# Test.net
KiCad netlist of a schematic drawn in Altium Designer
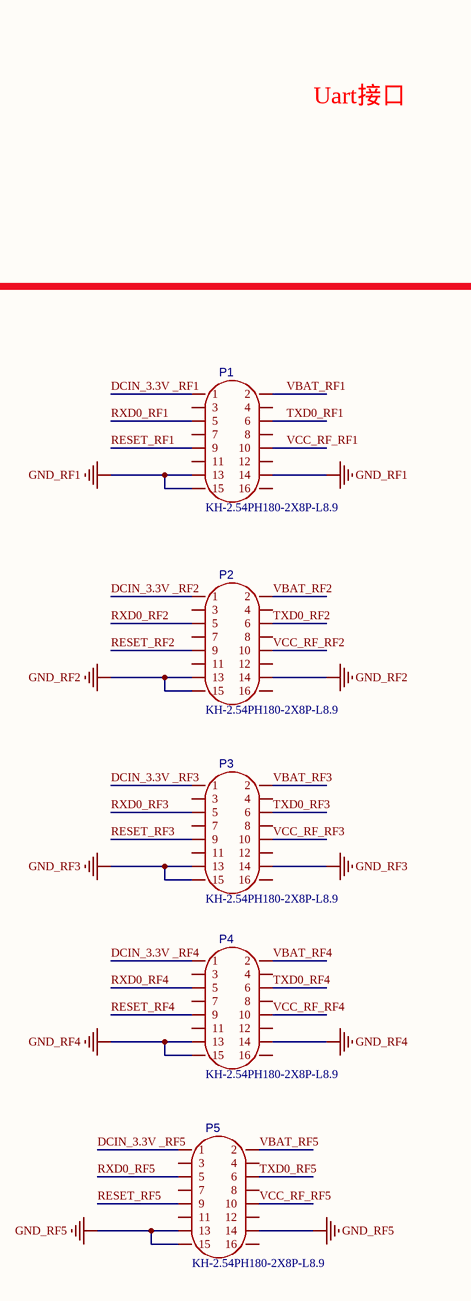
[diagram p0: Test.SchDoc, top left]
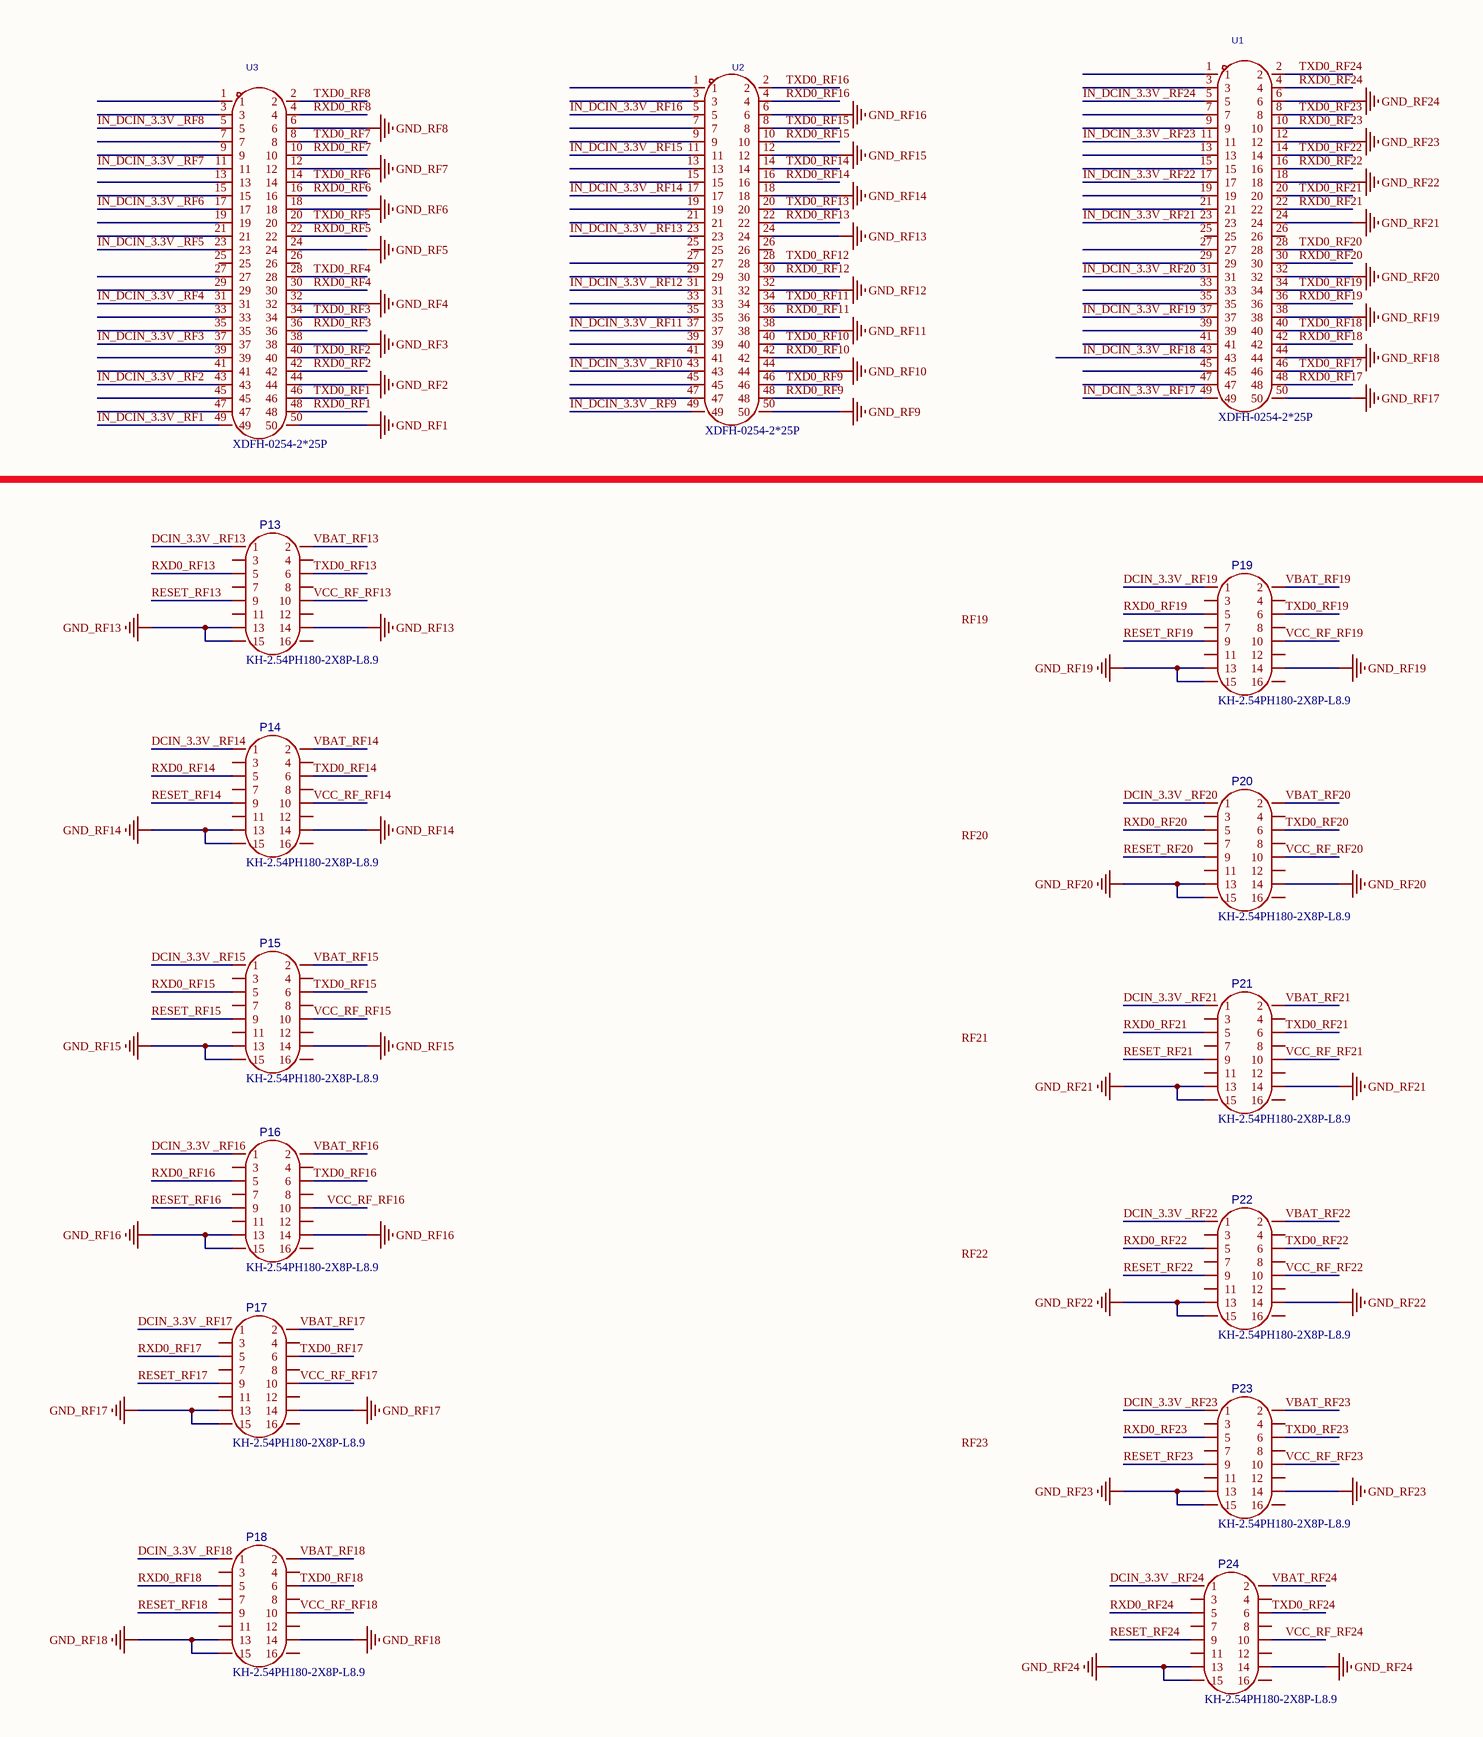
[diagram p1: Test.SchDoc, top middle]
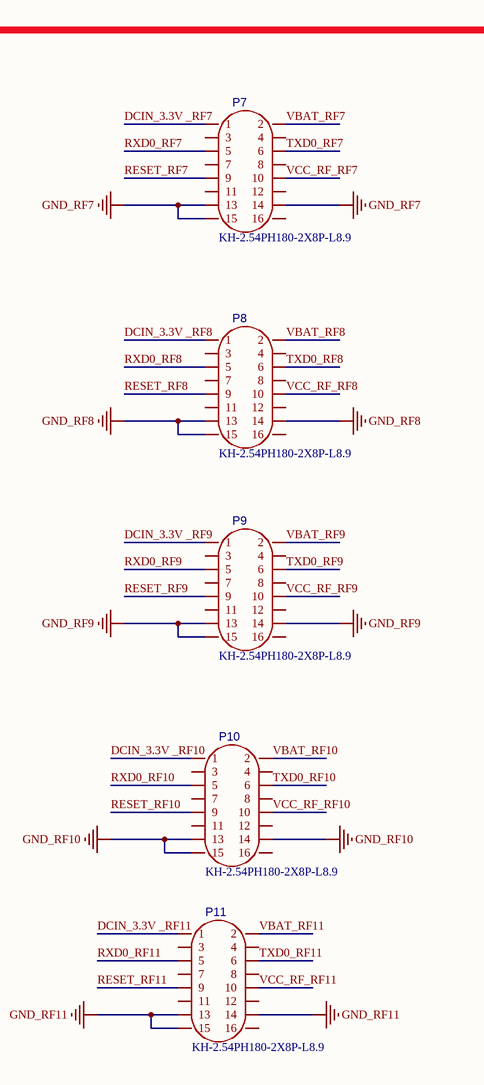
[diagram p2: Test.SchDoc, top right]
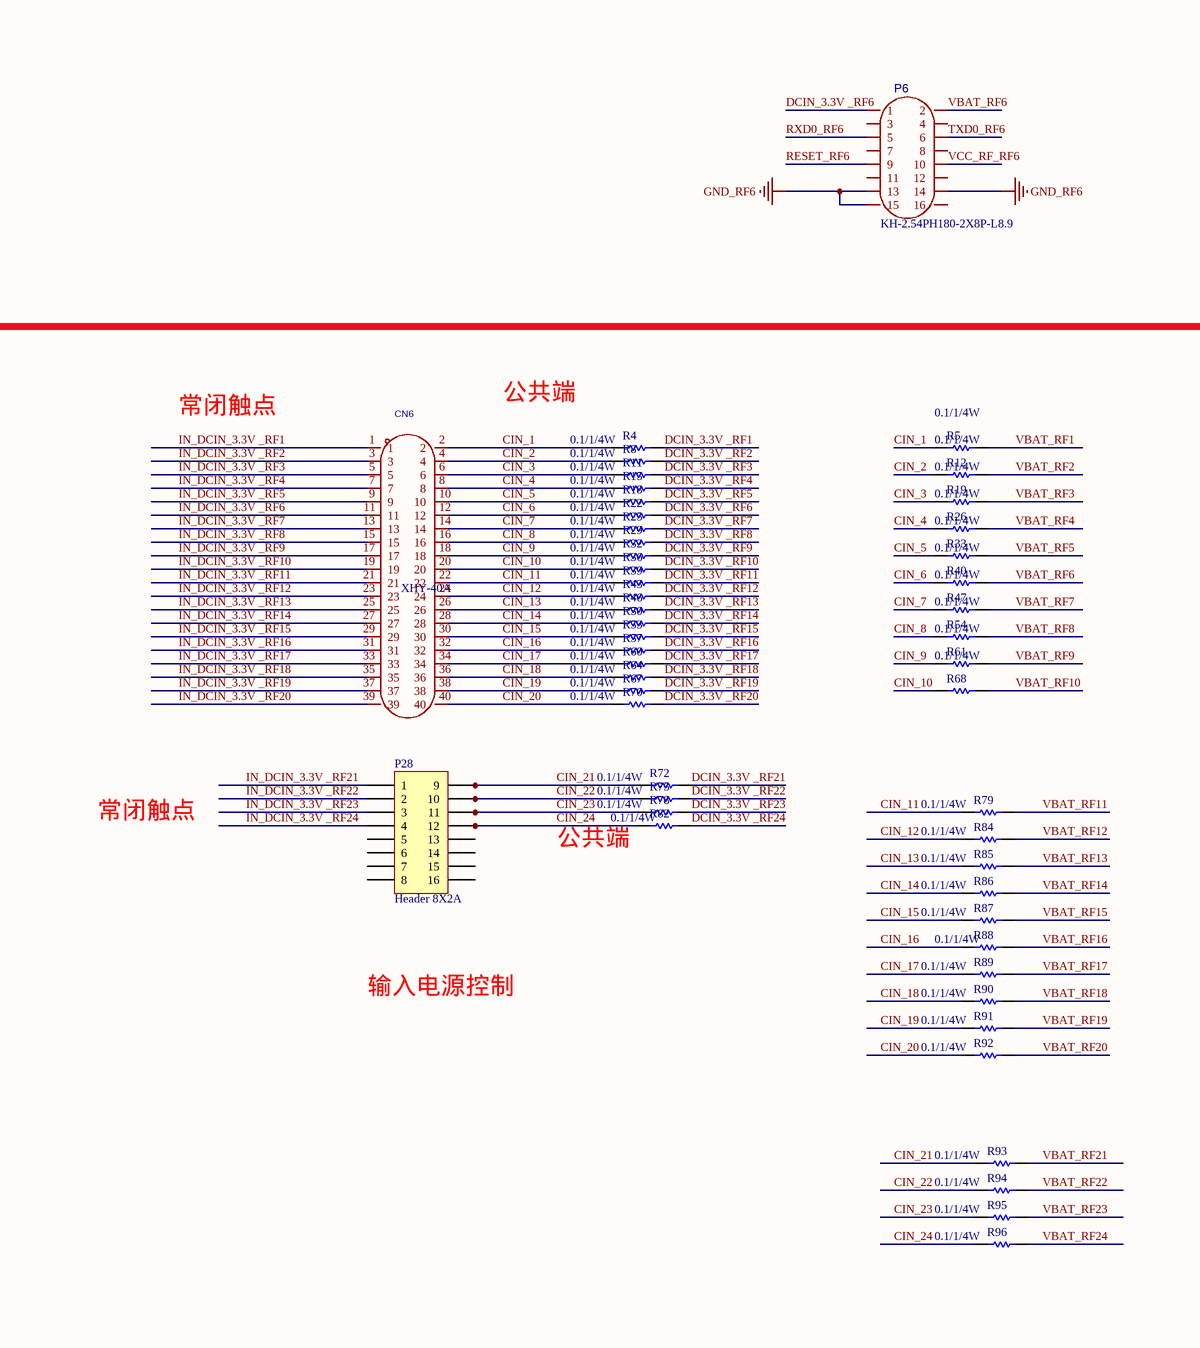
[diagram p3: Test.SchDoc, bottom left]
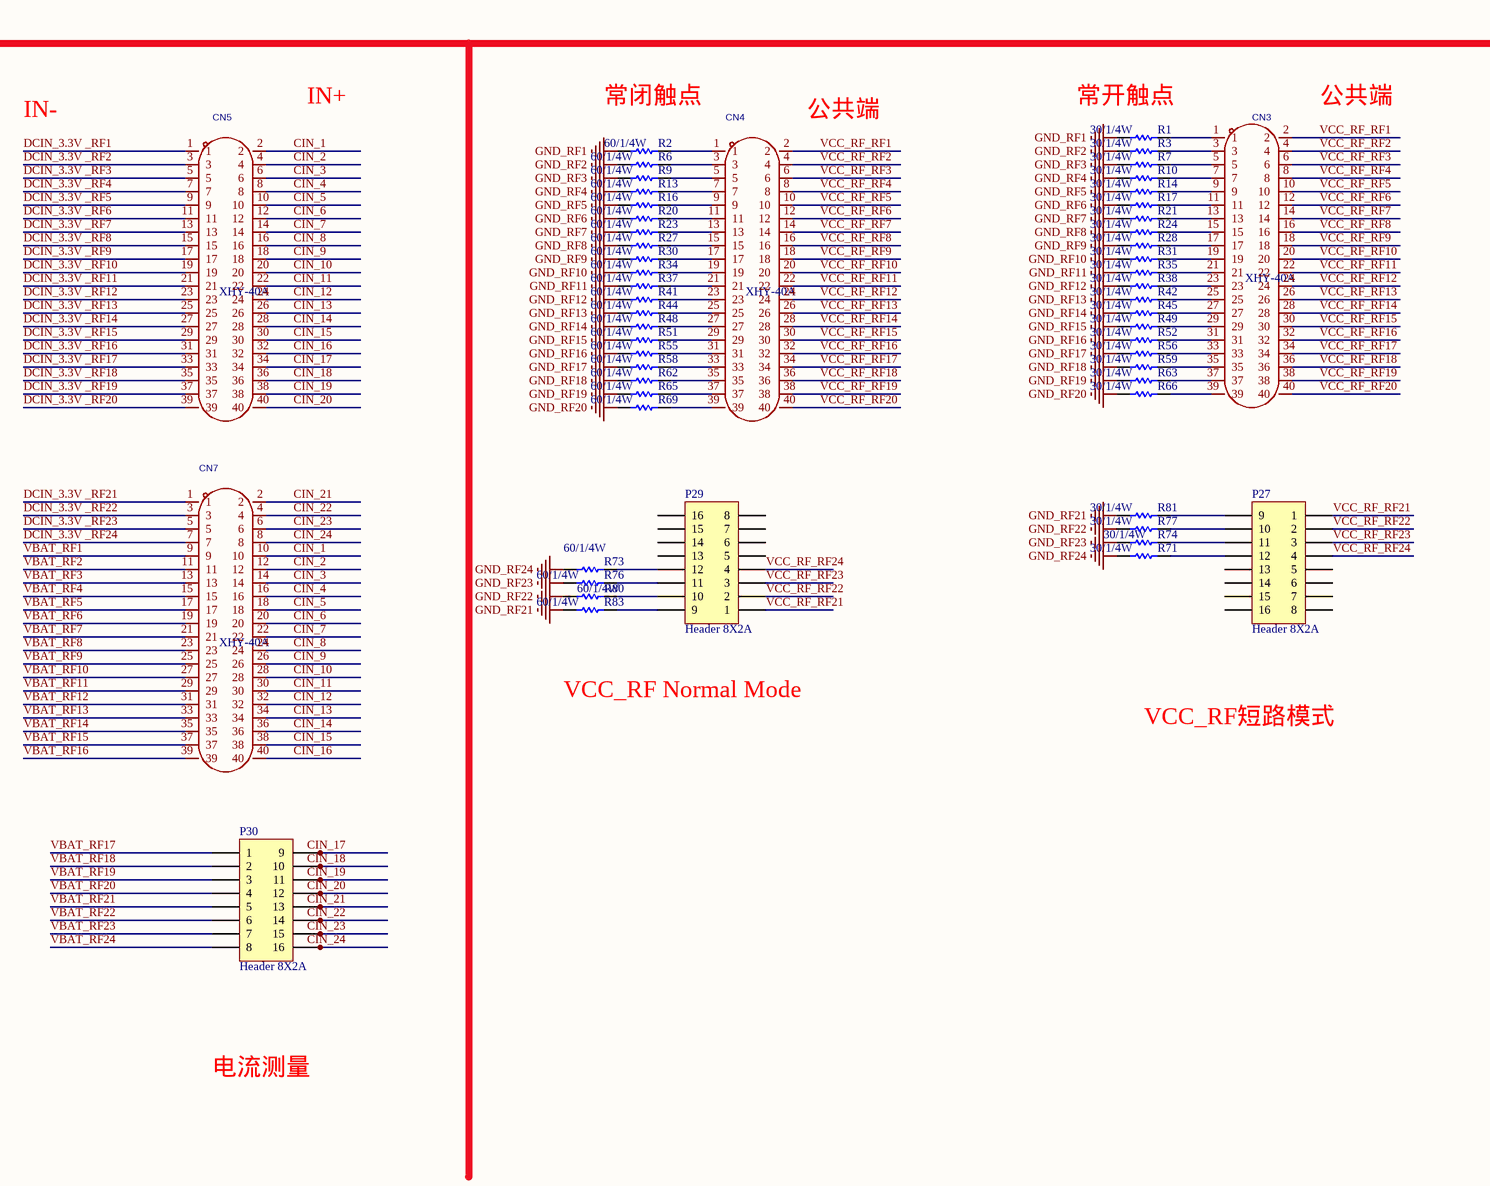
[diagram p4: Test.SchDoc, bottom middle]
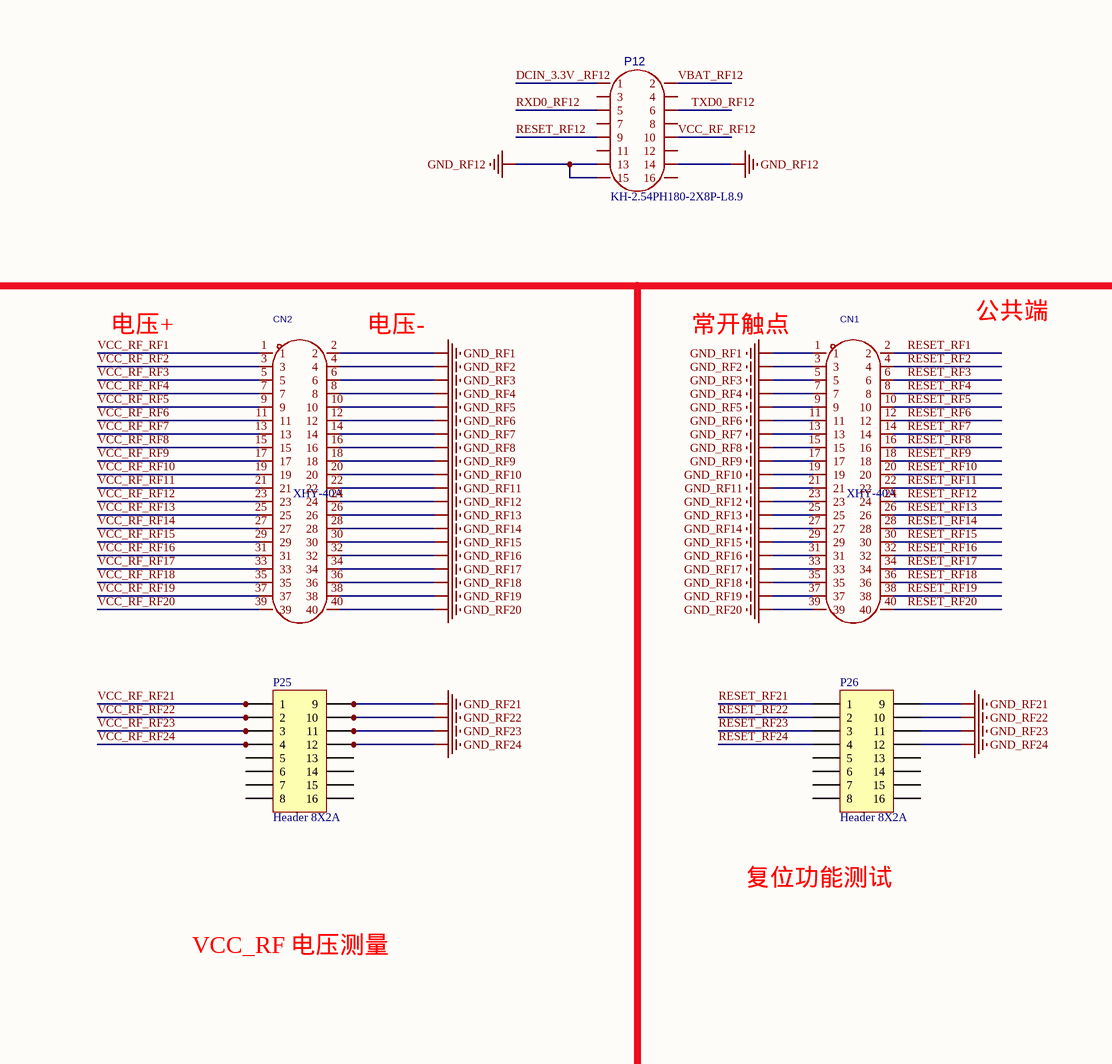
[diagram p5: Test.SchDoc, bottom right]

(export (version "E")
  (design (tool "Eeschema 10.0.6"))
  (components
    (comp (ref "CN1")
      (value "XHY-40A")
      (footprint "CONN-TH_XHY-40A:CONN-TH_XHY-40A")
      (libsource (lib "altium-import") (part "root_0_XHY-40A_"))
    )
    (comp (ref "CN2")
      (value "XHY-40A")
      (footprint "CONN-TH_XHY-40A:CONN-TH_XHY-40A")
      (libsource (lib "altium-import") (part "root_0_XHY-40A_"))
    )
    (comp (ref "CN3")
      (value "XHY-40A")
      (footprint "CONN-TH_XHY-40A:CONN-TH_XHY-40A")
      (libsource (lib "altium-import") (part "root_0_XHY-40A_"))
    )
    (comp (ref "CN4")
      (value "XHY-40A")
      (footprint "CONN-TH_XHY-40A:CONN-TH_XHY-40A")
      (libsource (lib "altium-import") (part "root_0_XHY-40A_"))
    )
    (comp (ref "CN5")
      (value "XHY-40A")
      (footprint "CONN-TH_XHY-40A:CONN-TH_XHY-40A")
      (libsource (lib "altium-import") (part "root_0_XHY-40A_"))
    )
    (comp (ref "CN6")
      (value "XHY-40A")
      (footprint "CONN-TH_XHY-40A:CONN-TH_XHY-40A")
      (libsource (lib "altium-import") (part "root_0_XHY-40A_"))
    )
    (comp (ref "CN7")
      (value "XHY-40A")
      (footprint "CONN-TH_XHY-40A:CONN-TH_XHY-40A")
      (libsource (lib "altium-import") (part "root_0_XHY-40A_"))
    )
    (comp (ref "P1")
      (value "KH-2.54PH180-2X8P-L8.9")
      (footprint "IDC-TH_16P-P2.54_C3406:IDC-TH_16P-P2.54_C3406")
      (libsource (lib "altium-import") (part "root_0_HDR-IDC-2.54-2X8P_"))
    )
    (comp (ref "P2")
      (value "KH-2.54PH180-2X8P-L8.9")
      (footprint "IDC-TH_16P-P2.54_C3406:IDC-TH_16P-P2.54_C3406")
      (libsource (lib "altium-import") (part "root_0_HDR-IDC-2.54-2X8P_"))
    )
    (comp (ref "P3")
      (value "KH-2.54PH180-2X8P-L8.9")
      (footprint "IDC-TH_16P-P2.54_C3406:IDC-TH_16P-P2.54_C3406")
      (libsource (lib "altium-import") (part "root_0_HDR-IDC-2.54-2X8P_"))
    )
    (comp (ref "P4")
      (value "KH-2.54PH180-2X8P-L8.9")
      (footprint "IDC-TH_16P-P2.54_C3406:IDC-TH_16P-P2.54_C3406")
      (libsource (lib "altium-import") (part "root_0_HDR-IDC-2.54-2X8P_"))
    )
    (comp (ref "P5")
      (value "KH-2.54PH180-2X8P-L8.9")
      (footprint "IDC-TH_16P-P2.54_C3406:IDC-TH_16P-P2.54_C3406")
      (libsource (lib "altium-import") (part "root_0_HDR-IDC-2.54-2X8P_"))
    )
    (comp (ref "P6")
      (value "KH-2.54PH180-2X8P-L8.9")
      (footprint "IDC-TH_16P-P2.54_C3406:IDC-TH_16P-P2.54_C3406")
      (libsource (lib "altium-import") (part "root_0_HDR-IDC-2.54-2X8P_"))
    )
    (comp (ref "P7")
      (value "KH-2.54PH180-2X8P-L8.9")
      (footprint "IDC-TH_16P-P2.54_C3406:IDC-TH_16P-P2.54_C3406")
      (libsource (lib "altium-import") (part "root_0_HDR-IDC-2.54-2X8P_"))
    )
    (comp (ref "P8")
      (value "KH-2.54PH180-2X8P-L8.9")
      (footprint "IDC-TH_16P-P2.54_C3406:IDC-TH_16P-P2.54_C3406")
      (libsource (lib "altium-import") (part "root_0_HDR-IDC-2.54-2X8P_"))
    )
    (comp (ref "P9")
      (value "KH-2.54PH180-2X8P-L8.9")
      (footprint "IDC-TH_16P-P2.54_C3406:IDC-TH_16P-P2.54_C3406")
      (libsource (lib "altium-import") (part "root_0_HDR-IDC-2.54-2X8P_"))
    )
    (comp (ref "P10")
      (value "KH-2.54PH180-2X8P-L8.9")
      (footprint "IDC-TH_16P-P2.54_C3406:IDC-TH_16P-P2.54_C3406")
      (libsource (lib "altium-import") (part "root_0_HDR-IDC-2.54-2X8P_"))
    )
    (comp (ref "P11")
      (value "KH-2.54PH180-2X8P-L8.9")
      (footprint "IDC-TH_16P-P2.54_C3406:IDC-TH_16P-P2.54_C3406")
      (libsource (lib "altium-import") (part "root_0_HDR-IDC-2.54-2X8P_"))
    )
    (comp (ref "P12")
      (value "KH-2.54PH180-2X8P-L8.9")
      (footprint "IDC-TH_16P-P2.54_C3406:IDC-TH_16P-P2.54_C3406")
      (libsource (lib "altium-import") (part "root_0_HDR-IDC-2.54-2X8P_"))
    )
    (comp (ref "P13")
      (value "KH-2.54PH180-2X8P-L8.9")
      (footprint "IDC-TH_16P-P2.54_C3406:IDC-TH_16P-P2.54_C3406")
      (libsource (lib "altium-import") (part "root_0_HDR-IDC-2.54-2X8P_"))
    )
    (comp (ref "P14")
      (value "KH-2.54PH180-2X8P-L8.9")
      (footprint "IDC-TH_16P-P2.54_C3406:IDC-TH_16P-P2.54_C3406")
      (libsource (lib "altium-import") (part "root_0_HDR-IDC-2.54-2X8P_"))
    )
    (comp (ref "P15")
      (value "KH-2.54PH180-2X8P-L8.9")
      (footprint "IDC-TH_16P-P2.54_C3406:IDC-TH_16P-P2.54_C3406")
      (libsource (lib "altium-import") (part "root_0_HDR-IDC-2.54-2X8P_"))
    )
    (comp (ref "P16")
      (value "KH-2.54PH180-2X8P-L8.9")
      (footprint "IDC-TH_16P-P2.54_C3406:IDC-TH_16P-P2.54_C3406")
      (libsource (lib "altium-import") (part "root_0_HDR-IDC-2.54-2X8P_"))
    )
    (comp (ref "P17")
      (value "KH-2.54PH180-2X8P-L8.9")
      (footprint "IDC-TH_16P-P2.54_C3406:IDC-TH_16P-P2.54_C3406")
      (libsource (lib "altium-import") (part "root_0_HDR-IDC-2.54-2X8P_"))
    )
    (comp (ref "P18")
      (value "KH-2.54PH180-2X8P-L8.9")
      (footprint "IDC-TH_16P-P2.54_C3406:IDC-TH_16P-P2.54_C3406")
      (libsource (lib "altium-import") (part "root_0_HDR-IDC-2.54-2X8P_"))
    )
    (comp (ref "P19")
      (value "KH-2.54PH180-2X8P-L8.9")
      (footprint "IDC-TH_16P-P2.54_C3406:IDC-TH_16P-P2.54_C3406")
      (libsource (lib "altium-import") (part "root_0_HDR-IDC-2.54-2X8P_"))
    )
    (comp (ref "P20")
      (value "KH-2.54PH180-2X8P-L8.9")
      (footprint "IDC-TH_16P-P2.54_C3406:IDC-TH_16P-P2.54_C3406")
      (libsource (lib "altium-import") (part "root_0_HDR-IDC-2.54-2X8P_"))
    )
    (comp (ref "P21")
      (value "KH-2.54PH180-2X8P-L8.9")
      (footprint "IDC-TH_16P-P2.54_C3406:IDC-TH_16P-P2.54_C3406")
      (libsource (lib "altium-import") (part "root_0_HDR-IDC-2.54-2X8P_"))
    )
    (comp (ref "P22")
      (value "KH-2.54PH180-2X8P-L8.9")
      (footprint "IDC-TH_16P-P2.54_C3406:IDC-TH_16P-P2.54_C3406")
      (libsource (lib "altium-import") (part "root_0_HDR-IDC-2.54-2X8P_"))
    )
    (comp (ref "P23")
      (value "KH-2.54PH180-2X8P-L8.9")
      (footprint "IDC-TH_16P-P2.54_C3406:IDC-TH_16P-P2.54_C3406")
      (libsource (lib "altium-import") (part "root_0_HDR-IDC-2.54-2X8P_"))
    )
    (comp (ref "P24")
      (value "KH-2.54PH180-2X8P-L8.9")
      (footprint "IDC-TH_16P-P2.54_C3406:IDC-TH_16P-P2.54_C3406")
      (libsource (lib "altium-import") (part "root_0_HDR-IDC-2.54-2X8P_"))
    )
    (comp (ref "P25")
      (value "Header 8X2A")
      (footprint "HDR2X8_CEN")
      (description "Header, 8-Pin, Dual row")
      (fields (field (name "PUBLISHER") "Altium Limited"))
      (libsource (lib "Miscellaneous Connectors") (part "Header 8X2A"))
    )
    (comp (ref "P26")
      (value "Header 8X2A")
      (footprint "HDR2X8_CEN")
      (description "Header, 8-Pin, Dual row")
      (fields (field (name "PUBLISHER") "Altium Limited"))
      (libsource (lib "Miscellaneous Connectors") (part "Header 8X2A"))
    )
    (comp (ref "P27")
      (value "Header 8X2A")
      (footprint "HDR2X8_CEN")
      (description "Header, 8-Pin, Dual row")
      (fields (field (name "PUBLISHER") "Altium Limited"))
      (libsource (lib "") (part "Header 8X2A_2"))
    )
    (comp (ref "P28")
      (value "Header 8X2A")
      (footprint "HDR2X8_CEN")
      (description "Header, 8-Pin, Dual row")
      (fields (field (name "PUBLISHER") "Altium Limited"))
      (libsource (lib "Miscellaneous Connectors") (part "Header 8X2A"))
    )
    (comp (ref "P29")
      (value "Header 8X2A")
      (footprint "HDR2X8_CEN")
      (description "Header, 8-Pin, Dual row")
      (fields (field (name "PUBLISHER") "Altium Limited"))
      (libsource (lib "") (part "Header 8X2A_1"))
    )
    (comp (ref "P30")
      (value "Header 8X2A")
      (footprint "HDR2X8_CEN")
      (description "Header, 8-Pin, Dual row")
      (fields (field (name "PUBLISHER") "Altium Limited"))
      (libsource (lib "Miscellaneous Connectors") (part "Header 8X2A"))
    )
    (comp (ref "R1")
      (value "30/1/4W")
      (footprint "1206R")
      (description "Resistor")
      (fields (field (name "PUBLISHER") "Altium Limited"))
      (libsource (lib "Miscellaneous Devices") (part "Res1"))
    )
    (comp (ref "R2")
      (value "60/1/4W")
      (footprint "1206R")
      (description "Resistor")
      (fields (field (name "PUBLISHER") "Altium Limited"))
      (libsource (lib "Miscellaneous Devices") (part "Res1"))
    )
    (comp (ref "R3")
      (value "30/1/4W")
      (footprint "1206R")
      (description "Resistor")
      (fields (field (name "PUBLISHER") "Altium Limited"))
      (libsource (lib "Miscellaneous Devices") (part "Res1"))
    )
    (comp (ref "R4")
      (value "0.1/1/4W")
      (footprint "1206R")
      (description "Resistor")
      (fields (field (name "PUBLISHER") "Altium Limited"))
      (libsource (lib "Miscellaneous Devices") (part "Res1"))
    )
    (comp (ref "R5")
      (value "0.1/1/4W")
      (footprint "1206R")
      (description "Resistor")
      (fields (field (name "PUBLISHER") "Altium Limited"))
      (libsource (lib "Miscellaneous Devices") (part "Res1"))
    )
    (comp (ref "R6")
      (value "60/1/4W")
      (footprint "1206R")
      (description "Resistor")
      (fields (field (name "PUBLISHER") "Altium Limited"))
      (libsource (lib "Miscellaneous Devices") (part "Res1"))
    )
    (comp (ref "R7")
      (value "30/1/4W")
      (footprint "1206R")
      (description "Resistor")
      (fields (field (name "PUBLISHER") "Altium Limited"))
      (libsource (lib "Miscellaneous Devices") (part "Res1"))
    )
    (comp (ref "R8")
      (value "0.1/1/4W")
      (footprint "1206R")
      (description "Resistor")
      (fields (field (name "PUBLISHER") "Altium Limited"))
      (libsource (lib "Miscellaneous Devices") (part "Res1"))
    )
    (comp (ref "R9")
      (value "60/1/4W")
      (footprint "1206R")
      (description "Resistor")
      (fields (field (name "PUBLISHER") "Altium Limited"))
      (libsource (lib "Miscellaneous Devices") (part "Res1"))
    )
    (comp (ref "R10")
      (value "30/1/4W")
      (footprint "1206R")
      (description "Resistor")
      (fields (field (name "PUBLISHER") "Altium Limited"))
      (libsource (lib "Miscellaneous Devices") (part "Res1"))
    )
    (comp (ref "R11")
      (value "0.1/1/4W")
      (footprint "1206R")
      (description "Resistor")
      (fields (field (name "PUBLISHER") "Altium Limited"))
      (libsource (lib "Miscellaneous Devices") (part "Res1"))
    )
    (comp (ref "R12")
      (value "0.1/1/4W")
      (footprint "1206R")
      (description "Resistor")
      (fields (field (name "PUBLISHER") "Altium Limited"))
      (libsource (lib "Miscellaneous Devices") (part "Res1"))
    )
    (comp (ref "R13")
      (value "60/1/4W")
      (footprint "1206R")
      (description "Resistor")
      (fields (field (name "PUBLISHER") "Altium Limited"))
      (libsource (lib "Miscellaneous Devices") (part "Res1"))
    )
    (comp (ref "R14")
      (value "30/1/4W")
      (footprint "1206R")
      (description "Resistor")
      (fields (field (name "PUBLISHER") "Altium Limited"))
      (libsource (lib "Miscellaneous Devices") (part "Res1"))
    )
    (comp (ref "R15")
      (value "0.1/1/4W")
      (footprint "1206R")
      (description "Resistor")
      (fields (field (name "PUBLISHER") "Altium Limited"))
      (libsource (lib "Miscellaneous Devices") (part "Res1"))
    )
    (comp (ref "R16")
      (value "60/1/4W")
      (footprint "1206R")
      (description "Resistor")
      (fields (field (name "PUBLISHER") "Altium Limited"))
      (libsource (lib "Miscellaneous Devices") (part "Res1"))
    )
    (comp (ref "R17")
      (value "30/1/4W")
      (footprint "1206R")
      (description "Resistor")
      (fields (field (name "PUBLISHER") "Altium Limited"))
      (libsource (lib "Miscellaneous Devices") (part "Res1"))
    )
    (comp (ref "R18")
      (value "0.1/1/4W")
      (footprint "1206R")
      (description "Resistor")
      (fields (field (name "PUBLISHER") "Altium Limited"))
      (libsource (lib "Miscellaneous Devices") (part "Res1"))
    )
    (comp (ref "R19")
      (value "0.1/1/4W")
      (footprint "1206R")
      (description "Resistor")
      (fields (field (name "PUBLISHER") "Altium Limited"))
      (libsource (lib "Miscellaneous Devices") (part "Res1"))
    )
    (comp (ref "R20")
      (value "60/1/4W")
      (footprint "1206R")
      (description "Resistor")
      (fields (field (name "PUBLISHER") "Altium Limited"))
      (libsource (lib "Miscellaneous Devices") (part "Res1"))
    )
    (comp (ref "R21")
      (value "30/1/4W")
      (footprint "1206R")
      (description "Resistor")
      (fields (field (name "PUBLISHER") "Altium Limited"))
      (libsource (lib "Miscellaneous Devices") (part "Res1"))
    )
    (comp (ref "R22")
      (value "0.1/1/4W")
      (footprint "1206R")
      (description "Resistor")
      (fields (field (name "PUBLISHER") "Altium Limited"))
      (libsource (lib "Miscellaneous Devices") (part "Res1"))
    )
    (comp (ref "R23")
      (value "60/1/4W")
      (footprint "1206R")
      (description "Resistor")
      (fields (field (name "PUBLISHER") "Altium Limited"))
      (libsource (lib "Miscellaneous Devices") (part "Res1"))
    )
    (comp (ref "R24")
      (value "30/1/4W")
      (footprint "1206R")
      (description "Resistor")
      (fields (field (name "PUBLISHER") "Altium Limited"))
      (libsource (lib "Miscellaneous Devices") (part "Res1"))
    )
    (comp (ref "R25")
      (value "0.1/1/4W")
      (footprint "1206R")
      (description "Resistor")
      (fields (field (name "PUBLISHER") "Altium Limited"))
      (libsource (lib "Miscellaneous Devices") (part "Res1"))
    )
    (comp (ref "R26")
      (value "0.1/1/4W")
      (footprint "1206R")
      (description "Resistor")
      (fields (field (name "PUBLISHER") "Altium Limited"))
      (libsource (lib "Miscellaneous Devices") (part "Res1"))
    )
    (comp (ref "R27")
      (value "60/1/4W")
      (footprint "1206R")
      (description "Resistor")
      (fields (field (name "PUBLISHER") "Altium Limited"))
      (libsource (lib "Miscellaneous Devices") (part "Res1"))
    )
    (comp (ref "R28")
      (value "30/1/4W")
      (footprint "1206R")
      (description "Resistor")
      (fields (field (name "PUBLISHER") "Altium Limited"))
      (libsource (lib "Miscellaneous Devices") (part "Res1"))
    )
    (comp (ref "R29")
      (value "0.1/1/4W")
      (footprint "1206R")
      (description "Resistor")
      (fields (field (name "PUBLISHER") "Altium Limited"))
      (libsource (lib "Miscellaneous Devices") (part "Res1"))
    )
    (comp (ref "R30")
      (value "60/1/4W")
      (footprint "1206R")
      (description "Resistor")
      (fields (field (name "PUBLISHER") "Altium Limited"))
      (libsource (lib "Miscellaneous Devices") (part "Res1"))
    )
    (comp (ref "R31")
      (value "30/1/4W")
      (footprint "1206R")
      (description "Resistor")
      (fields (field (name "PUBLISHER") "Altium Limited"))
      (libsource (lib "Miscellaneous Devices") (part "Res1"))
    )
    (comp (ref "R32")
      (value "0.1/1/4W")
      (footprint "1206R")
      (description "Resistor")
      (fields (field (name "PUBLISHER") "Altium Limited"))
      (libsource (lib "Miscellaneous Devices") (part "Res1"))
    )
    (comp (ref "R33")
      (value "0.1/1/4W")
      (footprint "1206R")
      (description "Resistor")
      (fields (field (name "PUBLISHER") "Altium Limited"))
      (libsource (lib "Miscellaneous Devices") (part "Res1"))
    )
    (comp (ref "R34")
      (value "60/1/4W")
      (footprint "1206R")
      (description "Resistor")
      (fields (field (name "PUBLISHER") "Altium Limited"))
      (libsource (lib "Miscellaneous Devices") (part "Res1"))
    )
    (comp (ref "R35")
      (value "30/1/4W")
      (footprint "1206R")
      (description "Resistor")
      (fields (field (name "PUBLISHER") "Altium Limited"))
      (libsource (lib "Miscellaneous Devices") (part "Res1"))
    )
    (comp (ref "R36")
      (value "0.1/1/4W")
      (footprint "1206R")
      (description "Resistor")
      (fields (field (name "PUBLISHER") "Altium Limited"))
      (libsource (lib "Miscellaneous Devices") (part "Res1"))
    )
    (comp (ref "R37")
      (value "60/1/4W")
      (footprint "1206R")
      (description "Resistor")
      (fields (field (name "PUBLISHER") "Altium Limited"))
      (libsource (lib "Miscellaneous Devices") (part "Res1"))
    )
    (comp (ref "R38")
      (value "30/1/4W")
      (footprint "1206R")
      (description "Resistor")
      (fields (field (name "PUBLISHER") "Altium Limited"))
      (libsource (lib "Miscellaneous Devices") (part "Res1"))
    )
    (comp (ref "R39")
      (value "0.1/1/4W")
      (footprint "1206R")
      (description "Resistor")
      (fields (field (name "PUBLISHER") "Altium Limited"))
      (libsource (lib "Miscellaneous Devices") (part "Res1"))
    )
    (comp (ref "R40")
      (value "0.1/1/4W")
      (footprint "1206R")
      (description "Resistor")
      (fields (field (name "PUBLISHER") "Altium Limited"))
      (libsource (lib "Miscellaneous Devices") (part "Res1"))
    )
    (comp (ref "R41")
      (value "60/1/4W")
      (footprint "1206R")
      (description "Resistor")
      (fields (field (name "PUBLISHER") "Altium Limited"))
      (libsource (lib "Miscellaneous Devices") (part "Res1"))
    )
    (comp (ref "R42")
      (value "30/1/4W")
      (footprint "1206R")
      (description "Resistor")
      (fields (field (name "PUBLISHER") "Altium Limited"))
      (libsource (lib "Miscellaneous Devices") (part "Res1"))
    )
    (comp (ref "R43")
      (value "0.1/1/4W")
      (footprint "1206R")
      (description "Resistor")
      (fields (field (name "PUBLISHER") "Altium Limited"))
      (libsource (lib "Miscellaneous Devices") (part "Res1"))
    )
    (comp (ref "R44")
      (value "60/1/4W")
      (footprint "1206R")
      (description "Resistor")
      (fields (field (name "PUBLISHER") "Altium Limited"))
      (libsource (lib "Miscellaneous Devices") (part "Res1"))
    )
    (comp (ref "R45")
      (value "30/1/4W")
      (footprint "1206R")
      (description "Resistor")
      (fields (field (name "PUBLISHER") "Altium Limited"))
      (libsource (lib "Miscellaneous Devices") (part "Res1"))
    )
    (comp (ref "R46")
      (value "0.1/1/4W")
      (footprint "1206R")
      (description "Resistor")
      (fields (field (name "PUBLISHER") "Altium Limited"))
      (libsource (lib "Miscellaneous Devices") (part "Res1"))
    )
    (comp (ref "R47")
      (value "0.1/1/4W")
      (footprint "1206R")
      (description "Resistor")
      (fields (field (name "PUBLISHER") "Altium Limited"))
      (libsource (lib "Miscellaneous Devices") (part "Res1"))
    )
    (comp (ref "R48")
      (value "60/1/4W")
      (footprint "1206R")
      (description "Resistor")
      (fields (field (name "PUBLISHER") "Altium Limited"))
      (libsource (lib "Miscellaneous Devices") (part "Res1"))
    )
    (comp (ref "R49")
      (value "30/1/4W")
      (footprint "1206R")
      (description "Resistor")
      (fields (field (name "PUBLISHER") "Altium Limited"))
      (libsource (lib "Miscellaneous Devices") (part "Res1"))
    )
    (comp (ref "R50")
      (value "0.1/1/4W")
      (footprint "1206R")
      (description "Resistor")
      (fields (field (name "PUBLISHER") "Altium Limited"))
      (libsource (lib "Miscellaneous Devices") (part "Res1"))
    )
    (comp (ref "R51")
      (value "60/1/4W")
      (footprint "1206R")
      (description "Resistor")
      (fields (field (name "PUBLISHER") "Altium Limited"))
      (libsource (lib "Miscellaneous Devices") (part "Res1"))
    )
    (comp (ref "R52")
      (value "30/1/4W")
      (footprint "1206R")
      (description "Resistor")
      (fields (field (name "PUBLISHER") "Altium Limited"))
      (libsource (lib "Miscellaneous Devices") (part "Res1"))
    )
    (comp (ref "R53")
      (value "0.1/1/4W")
      (footprint "1206R")
      (description "Resistor")
      (fields (field (name "PUBLISHER") "Altium Limited"))
      (libsource (lib "Miscellaneous Devices") (part "Res1"))
    )
    (comp (ref "R54")
      (value "0.1/1/4W")
      (footprint "1206R")
      (description "Resistor")
      (fields (field (name "PUBLISHER") "Altium Limited"))
      (libsource (lib "Miscellaneous Devices") (part "Res1"))
    )
    (comp (ref "R55")
      (value "60/1/4W")
      (footprint "1206R")
      (description "Resistor")
      (fields (field (name "PUBLISHER") "Altium Limited"))
      (libsource (lib "Miscellaneous Devices") (part "Res1"))
    )
    (comp (ref "R56")
      (value "30/1/4W")
      (footprint "1206R")
      (description "Resistor")
      (fields (field (name "PUBLISHER") "Altium Limited"))
      (libsource (lib "Miscellaneous Devices") (part "Res1"))
    )
    (comp (ref "R57")
      (value "0.1/1/4W")
      (footprint "1206R")
      (description "Resistor")
      (fields (field (name "PUBLISHER") "Altium Limited"))
      (libsource (lib "Miscellaneous Devices") (part "Res1"))
    )
    (comp (ref "R58")
      (value "60/1/4W")
      (footprint "1206R")
      (description "Resistor")
      (fields (field (name "PUBLISHER") "Altium Limited"))
      (libsource (lib "Miscellaneous Devices") (part "Res1"))
    )
    (comp (ref "R59")
      (value "30/1/4W")
      (footprint "1206R")
      (description "Resistor")
      (fields (field (name "PUBLISHER") "Altium Limited"))
      (libsource (lib "Miscellaneous Devices") (part "Res1"))
    )
    (comp (ref "R60")
      (value "0.1/1/4W")
      (footprint "1206R")
      (description "Resistor")
      (fields (field (name "PUBLISHER") "Altium Limited"))
      (libsource (lib "Miscellaneous Devices") (part "Res1"))
    )
    (comp (ref "R61")
      (value "0.1/1/4W")
      (footprint "1206R")
      (description "Resistor")
      (fields (field (name "PUBLISHER") "Altium Limited"))
      (libsource (lib "Miscellaneous Devices") (part "Res1"))
    )
    (comp (ref "R62")
      (value "60/1/4W")
      (footprint "1206R")
      (description "Resistor")
      (fields (field (name "PUBLISHER") "Altium Limited"))
      (libsource (lib "Miscellaneous Devices") (part "Res1"))
    )
    (comp (ref "R63")
      (value "30/1/4W")
      (footprint "1206R")
      (description "Resistor")
      (fields (field (name "PUBLISHER") "Altium Limited"))
      (libsource (lib "Miscellaneous Devices") (part "Res1"))
    )
    (comp (ref "R64")
      (value "0.1/1/4W")
      (footprint "1206R")
      (description "Resistor")
      (fields (field (name "PUBLISHER") "Altium Limited"))
      (libsource (lib "Miscellaneous Devices") (part "Res1"))
    )
    (comp (ref "R65")
      (value "60/1/4W")
      (footprint "1206R")
      (description "Resistor")
      (fields (field (name "PUBLISHER") "Altium Limited"))
      (libsource (lib "Miscellaneous Devices") (part "Res1"))
    )
    (comp (ref "R66")
      (value "30/1/4W")
      (footprint "1206R")
      (description "Resistor")
      (fields (field (name "PUBLISHER") "Altium Limited"))
      (libsource (lib "Miscellaneous Devices") (part "Res1"))
    )
    (comp (ref "R67")
      (value "0.1/1/4W")
      (footprint "1206R")
      (description "Resistor")
      (fields (field (name "PUBLISHER") "Altium Limited"))
      (libsource (lib "Miscellaneous Devices") (part "Res1"))
    )
    (comp (ref "R68")
      (value "0.1/1/4W")
      (footprint "1206R")
      (description "Resistor")
      (fields (field (name "PUBLISHER") "Altium Limited"))
      (libsource (lib "Miscellaneous Devices") (part "Res1"))
    )
    (comp (ref "R69")
      (value "60/1/4W")
      (footprint "1206R")
      (description "Resistor")
      (fields (field (name "PUBLISHER") "Altium Limited"))
      (libsource (lib "Miscellaneous Devices") (part "Res1"))
    )
    (comp (ref "R70")
      (value "0.1/1/4W")
      (footprint "1206R")
      (description "Resistor")
      (fields (field (name "PUBLISHER") "Altium Limited"))
      (libsource (lib "Miscellaneous Devices") (part "Res1"))
    )
    (comp (ref "R71")
      (value "30/1/4W")
      (footprint "1206R")
      (description "Resistor")
      (fields (field (name "PUBLISHER") "Altium Limited"))
      (libsource (lib "Miscellaneous Devices") (part "Res1"))
    )
    (comp (ref "R72")
      (value "0.1/1/4W")
      (footprint "1206R")
      (description "Resistor")
      (fields (field (name "PUBLISHER") "Altium Limited"))
      (libsource (lib "Miscellaneous Devices") (part "Res1"))
    )
    (comp (ref "R73")
      (value "60/1/4W")
      (footprint "1206R")
      (description "Resistor")
      (fields (field (name "PUBLISHER") "Altium Limited"))
      (libsource (lib "Miscellaneous Devices") (part "Res1"))
    )
    (comp (ref "R74")
      (value "30/1/4W")
      (footprint "1206R")
      (description "Resistor")
      (fields (field (name "PUBLISHER") "Altium Limited"))
      (libsource (lib "Miscellaneous Devices") (part "Res1"))
    )
    (comp (ref "R75")
      (value "0.1/1/4W")
      (footprint "1206R")
      (description "Resistor")
      (fields (field (name "PUBLISHER") "Altium Limited"))
      (libsource (lib "Miscellaneous Devices") (part "Res1"))
    )
    (comp (ref "R76")
      (value "60/1/4W")
      (footprint "1206R")
      (description "Resistor")
      (fields (field (name "PUBLISHER") "Altium Limited"))
      (libsource (lib "Miscellaneous Devices") (part "Res1"))
    )
    (comp (ref "R77")
      (value "30/1/4W")
      (footprint "1206R")
      (description "Resistor")
      (fields (field (name "PUBLISHER") "Altium Limited"))
      (libsource (lib "Miscellaneous Devices") (part "Res1"))
    )
    (comp (ref "R78")
      (value "0.1/1/4W")
      (footprint "1206R")
      (description "Resistor")
      (fields (field (name "PUBLISHER") "Altium Limited"))
      (libsource (lib "Miscellaneous Devices") (part "Res1"))
    )
    (comp (ref "R79")
      (value "0.1/1/4W")
      (footprint "1206R")
      (description "Resistor")
      (fields (field (name "PUBLISHER") "Altium Limited"))
      (libsource (lib "Miscellaneous Devices") (part "Res1"))
    )
    (comp (ref "R80")
      (value "60/1/4W")
      (footprint "1206R")
      (description "Resistor")
      (fields (field (name "PUBLISHER") "Altium Limited"))
      (libsource (lib "Miscellaneous Devices") (part "Res1"))
    )
    (comp (ref "R81")
      (value "30/1/4W")
      (footprint "1206R")
      (description "Resistor")
      (fields (field (name "PUBLISHER") "Altium Limited"))
      (libsource (lib "Miscellaneous Devices") (part "Res1"))
    )
    (comp (ref "R82")
      (value "0.1/1/4W")
      (footprint "1206R")
      (description "Resistor")
      (fields (field (name "PUBLISHER") "Altium Limited"))
      (libsource (lib "Miscellaneous Devices") (part "Res1"))
    )
    (comp (ref "R83")
      (value "60/1/4W")
      (footprint "1206R")
      (description "Resistor")
      (fields (field (name "PUBLISHER") "Altium Limited"))
      (libsource (lib "Miscellaneous Devices") (part "Res1"))
    )
    (comp (ref "R84")
      (value "0.1/1/4W")
      (footprint "1206R")
      (description "Resistor")
      (fields (field (name "PUBLISHER") "Altium Limited"))
      (libsource (lib "Miscellaneous Devices") (part "Res1"))
    )
    (comp (ref "R85")
      (value "0.1/1/4W")
      (footprint "1206R")
      (description "Resistor")
      (fields (field (name "PUBLISHER") "Altium Limited"))
      (libsource (lib "Miscellaneous Devices") (part "Res1"))
    )
    (comp (ref "R86")
      (value "0.1/1/4W")
      (footprint "1206R")
      (description "Resistor")
      (fields (field (name "PUBLISHER") "Altium Limited"))
      (libsource (lib "Miscellaneous Devices") (part "Res1"))
    )
    (comp (ref "R87")
      (value "0.1/1/4W")
      (footprint "1206R")
      (description "Resistor")
      (fields (field (name "PUBLISHER") "Altium Limited"))
      (libsource (lib "Miscellaneous Devices") (part "Res1"))
    )
    (comp (ref "R88")
      (value "0.1/1/4W")
      (footprint "1206R")
      (description "Resistor")
      (fields (field (name "PUBLISHER") "Altium Limited"))
      (libsource (lib "Miscellaneous Devices") (part "Res1"))
    )
    (comp (ref "R89")
      (value "0.1/1/4W")
      (footprint "1206R")
      (description "Resistor")
      (fields (field (name "PUBLISHER") "Altium Limited"))
      (libsource (lib "Miscellaneous Devices") (part "Res1"))
    )
    (comp (ref "R90")
      (value "0.1/1/4W")
      (footprint "1206R")
      (description "Resistor")
      (fields (field (name "PUBLISHER") "Altium Limited"))
      (libsource (lib "Miscellaneous Devices") (part "Res1"))
    )
    (comp (ref "R91")
      (value "0.1/1/4W")
      (footprint "1206R")
      (description "Resistor")
      (fields (field (name "PUBLISHER") "Altium Limited"))
      (libsource (lib "Miscellaneous Devices") (part "Res1"))
    )
    (comp (ref "R92")
      (value "0.1/1/4W")
      (footprint "1206R")
      (description "Resistor")
      (fields (field (name "PUBLISHER") "Altium Limited"))
      (libsource (lib "Miscellaneous Devices") (part "Res1"))
    )
    (comp (ref "R93")
      (value "0.1/1/4W")
      (footprint "1206R")
      (description "Resistor")
      (fields (field (name "PUBLISHER") "Altium Limited"))
      (libsource (lib "Miscellaneous Devices") (part "Res1"))
    )
    (comp (ref "R94")
      (value "0.1/1/4W")
      (footprint "1206R")
      (description "Resistor")
      (fields (field (name "PUBLISHER") "Altium Limited"))
      (libsource (lib "Miscellaneous Devices") (part "Res1"))
    )
    (comp (ref "R95")
      (value "0.1/1/4W")
      (footprint "1206R")
      (description "Resistor")
      (fields (field (name "PUBLISHER") "Altium Limited"))
      (libsource (lib "Miscellaneous Devices") (part "Res1"))
    )
    (comp (ref "R96")
      (value "0.1/1/4W")
      (footprint "1206R")
      (description "Resistor")
      (fields (field (name "PUBLISHER") "Altium Limited"))
      (libsource (lib "Miscellaneous Devices") (part "Res1"))
    )
    (comp (ref "U1")
      (value "XDFH-0254-2*25P")
      (footprint "CONN-TH_50P-P2.54_LX_XDFH-0254-2X25P:CONN-TH_50P-P2.54_LX_XDFH-0254-2X25P")
      (libsource (lib "altium-import") (part "root_0_XDFH-0254- 2*25P_"))
    )
    (comp (ref "U2")
      (value "XDFH-0254-2*25P")
      (footprint "CONN-TH_50P-P2.54_LX_XDFH-0254-2X25P:CONN-TH_50P-P2.54_LX_XDFH-0254-2X25P")
      (libsource (lib "altium-import") (part "root_0_XDFH-0254- 2*25P_"))
    )
    (comp (ref "U3")
      (value "XDFH-0254-2*25P")
      (footprint "CONN-TH_50P-P2.54_LX_XDFH-0254-2X25P:CONN-TH_50P-P2.54_LX_XDFH-0254-2X25P")
      (libsource (lib "altium-import") (part "root_0_XDFH-0254- 2*25P_"))
    )
  )
  (nets
    (net (code "1") (name "/CIN_1") (class "Default")
      (node (ref "CN5") (pin "2") (pinfunction "2_2") (pintype "passive"))
      (node (ref "CN6") (pin "2") (pinfunction "2_2") (pintype "passive"))
      (node (ref "CN7") (pin "10") (pinfunction "10_10") (pintype "passive"))
      (node (ref "R4") (pin "1") (pinfunction "1_1") (pintype "passive"))
      (node (ref "R5") (pin "1") (pinfunction "1_1") (pintype "passive"))
    )
    (net (code "2") (name "/CIN_2") (class "Default")
      (node (ref "CN5") (pin "4") (pinfunction "4_4") (pintype "passive"))
      (node (ref "CN6") (pin "4") (pinfunction "4_4") (pintype "passive"))
      (node (ref "CN7") (pin "12") (pinfunction "12_12") (pintype "passive"))
      (node (ref "R12") (pin "1") (pinfunction "1_1") (pintype "passive"))
      (node (ref "R8") (pin "1") (pinfunction "1_1") (pintype "passive"))
    )
    (net (code "3") (name "/CIN_3") (class "Default")
      (node (ref "CN5") (pin "6") (pinfunction "6_6") (pintype "passive"))
      (node (ref "CN6") (pin "6") (pinfunction "6_6") (pintype "passive"))
      (node (ref "CN7") (pin "14") (pinfunction "14_14") (pintype "passive"))
      (node (ref "R11") (pin "1") (pinfunction "1_1") (pintype "passive"))
      (node (ref "R19") (pin "1") (pinfunction "1_1") (pintype "passive"))
    )
    (net (code "4") (name "/CIN_4") (class "Default")
      (node (ref "CN5") (pin "8") (pinfunction "8_8") (pintype "passive"))
      (node (ref "CN6") (pin "8") (pinfunction "8_8") (pintype "passive"))
      (node (ref "CN7") (pin "16") (pinfunction "16_16") (pintype "passive"))
      (node (ref "R15") (pin "1") (pinfunction "1_1") (pintype "passive"))
      (node (ref "R26") (pin "1") (pinfunction "1_1") (pintype "passive"))
    )
    (net (code "5") (name "/CIN_5") (class "Default")
      (node (ref "CN5") (pin "10") (pinfunction "10_10") (pintype "passive"))
      (node (ref "CN6") (pin "10") (pinfunction "10_10") (pintype "passive"))
      (node (ref "CN7") (pin "18") (pinfunction "18_18") (pintype "passive"))
      (node (ref "R18") (pin "1") (pinfunction "1_1") (pintype "passive"))
      (node (ref "R33") (pin "1") (pinfunction "1_1") (pintype "passive"))
    )
    (net (code "6") (name "/CIN_6") (class "Default")
      (node (ref "CN5") (pin "12") (pinfunction "12_12") (pintype "passive"))
      (node (ref "CN6") (pin "12") (pinfunction "12_12") (pintype "passive"))
      (node (ref "CN7") (pin "20") (pinfunction "20_20") (pintype "passive"))
      (node (ref "R22") (pin "1") (pinfunction "1_1") (pintype "passive"))
      (node (ref "R40") (pin "1") (pinfunction "1_1") (pintype "passive"))
    )
    (net (code "7") (name "/CIN_7") (class "Default")
      (node (ref "CN5") (pin "14") (pinfunction "14_14") (pintype "passive"))
      (node (ref "CN6") (pin "14") (pinfunction "14_14") (pintype "passive"))
      (node (ref "CN7") (pin "22") (pinfunction "22_22") (pintype "passive"))
      (node (ref "R25") (pin "1") (pinfunction "1_1") (pintype "passive"))
      (node (ref "R47") (pin "1") (pinfunction "1_1") (pintype "passive"))
    )
    (net (code "8") (name "/CIN_8") (class "Default")
      (node (ref "CN5") (pin "16") (pinfunction "16_16") (pintype "passive"))
      (node (ref "CN6") (pin "16") (pinfunction "16_16") (pintype "passive"))
      (node (ref "CN7") (pin "24") (pinfunction "24_24") (pintype "passive"))
      (node (ref "R29") (pin "1") (pinfunction "1_1") (pintype "passive"))
      (node (ref "R54") (pin "1") (pinfunction "1_1") (pintype "passive"))
    )
    (net (code "9") (name "/CIN_9") (class "Default")
      (node (ref "CN5") (pin "18") (pinfunction "18_18") (pintype "passive"))
      (node (ref "CN6") (pin "18") (pinfunction "18_18") (pintype "passive"))
      (node (ref "CN7") (pin "26") (pinfunction "26_26") (pintype "passive"))
      (node (ref "R32") (pin "1") (pinfunction "1_1") (pintype "passive"))
      (node (ref "R61") (pin "1") (pinfunction "1_1") (pintype "passive"))
    )
    (net (code "10") (name "/CIN_10") (class "Default")
      (node (ref "CN5") (pin "20") (pinfunction "20_20") (pintype "passive"))
      (node (ref "CN6") (pin "20") (pinfunction "20_20") (pintype "passive"))
      (node (ref "CN7") (pin "28") (pinfunction "28_28") (pintype "passive"))
      (node (ref "R36") (pin "1") (pinfunction "1_1") (pintype "passive"))
      (node (ref "R68") (pin "1") (pinfunction "1_1") (pintype "passive"))
    )
    (net (code "11") (name "/CIN_11") (class "Default")
      (node (ref "CN5") (pin "22") (pinfunction "22_22") (pintype "passive"))
      (node (ref "CN6") (pin "22") (pinfunction "22_22") (pintype "passive"))
      (node (ref "CN7") (pin "30") (pinfunction "30_30") (pintype "passive"))
      (node (ref "R39") (pin "1") (pinfunction "1_1") (pintype "passive"))
      (node (ref "R79") (pin "1") (pinfunction "1_1") (pintype "passive"))
    )
    (net (code "12") (name "/CIN_12") (class "Default")
      (node (ref "CN5") (pin "24") (pinfunction "24_24") (pintype "passive"))
      (node (ref "CN6") (pin "24") (pinfunction "24_24") (pintype "passive"))
      (node (ref "CN7") (pin "32") (pinfunction "32_32") (pintype "passive"))
      (node (ref "R43") (pin "1") (pinfunction "1_1") (pintype "passive"))
      (node (ref "R84") (pin "1") (pinfunction "1_1") (pintype "passive"))
    )
    (net (code "13") (name "/CIN_13") (class "Default")
      (node (ref "CN5") (pin "26") (pinfunction "26_26") (pintype "passive"))
      (node (ref "CN6") (pin "26") (pinfunction "26_26") (pintype "passive"))
      (node (ref "CN7") (pin "34") (pinfunction "34_34") (pintype "passive"))
      (node (ref "R46") (pin "1") (pinfunction "1_1") (pintype "passive"))
      (node (ref "R85") (pin "1") (pinfunction "1_1") (pintype "passive"))
    )
    (net (code "14") (name "/CIN_14") (class "Default")
      (node (ref "CN5") (pin "28") (pinfunction "28_28") (pintype "passive"))
      (node (ref "CN6") (pin "28") (pinfunction "28_28") (pintype "passive"))
      (node (ref "CN7") (pin "36") (pinfunction "36_36") (pintype "passive"))
      (node (ref "R50") (pin "1") (pinfunction "1_1") (pintype "passive"))
      (node (ref "R86") (pin "1") (pinfunction "1_1") (pintype "passive"))
    )
    (net (code "15") (name "/CIN_15") (class "Default")
      (node (ref "CN5") (pin "30") (pinfunction "30_30") (pintype "passive"))
      (node (ref "CN6") (pin "30") (pinfunction "30_30") (pintype "passive"))
      (node (ref "CN7") (pin "38") (pinfunction "38_38") (pintype "passive"))
      (node (ref "R53") (pin "1") (pinfunction "1_1") (pintype "passive"))
      (node (ref "R87") (pin "1") (pinfunction "1_1") (pintype "passive"))
    )
    (net (code "16") (name "/CIN_16") (class "Default")
      (node (ref "CN5") (pin "32") (pinfunction "32_32") (pintype "passive"))
      (node (ref "CN6") (pin "32") (pinfunction "32_32") (pintype "passive"))
      (node (ref "CN7") (pin "40") (pinfunction "40_40") (pintype "passive"))
      (node (ref "R57") (pin "1") (pinfunction "1_1") (pintype "passive"))
      (node (ref "R88") (pin "1") (pinfunction "1_1") (pintype "passive"))
    )
    (net (code "17") (name "/CIN_17") (class "Default")
      (node (ref "CN5") (pin "34") (pinfunction "34_34") (pintype "passive"))
      (node (ref "CN6") (pin "34") (pinfunction "34_34") (pintype "passive"))
      (node (ref "P30") (pin "9") (pinfunction "9_9") (pintype "passive"))
      (node (ref "R60") (pin "1") (pinfunction "1_1") (pintype "passive"))
      (node (ref "R89") (pin "1") (pinfunction "1_1") (pintype "passive"))
    )
    (net (code "18") (name "/CIN_18") (class "Default")
      (node (ref "CN5") (pin "36") (pinfunction "36_36") (pintype "passive"))
      (node (ref "CN6") (pin "36") (pinfunction "36_36") (pintype "passive"))
      (node (ref "P30") (pin "10") (pinfunction "10_10") (pintype "passive"))
      (node (ref "R64") (pin "1") (pinfunction "1_1") (pintype "passive"))
      (node (ref "R90") (pin "1") (pinfunction "1_1") (pintype "passive"))
    )
    (net (code "19") (name "/CIN_19") (class "Default")
      (node (ref "CN5") (pin "38") (pinfunction "38_38") (pintype "passive"))
      (node (ref "CN6") (pin "38") (pinfunction "38_38") (pintype "passive"))
      (node (ref "P30") (pin "11") (pinfunction "11_11") (pintype "passive"))
      (node (ref "R67") (pin "1") (pinfunction "1_1") (pintype "passive"))
      (node (ref "R91") (pin "1") (pinfunction "1_1") (pintype "passive"))
    )
    (net (code "20") (name "/CIN_20") (class "Default")
      (node (ref "CN5") (pin "40") (pinfunction "40_40") (pintype "passive"))
      (node (ref "CN6") (pin "40") (pinfunction "40_40") (pintype "passive"))
      (node (ref "P30") (pin "12") (pinfunction "12_12") (pintype "passive"))
      (node (ref "R70") (pin "1") (pinfunction "1_1") (pintype "passive"))
      (node (ref "R92") (pin "1") (pinfunction "1_1") (pintype "passive"))
    )
    (net (code "21") (name "/CIN_21") (class "Default")
      (node (ref "CN7") (pin "2") (pinfunction "2_2") (pintype "passive"))
      (node (ref "P28") (pin "9") (pinfunction "9_9") (pintype "passive"))
      (node (ref "P30") (pin "13") (pinfunction "13_13") (pintype "passive"))
      (node (ref "R72") (pin "1") (pinfunction "1_1") (pintype "passive"))
      (node (ref "R93") (pin "1") (pinfunction "1_1") (pintype "passive"))
    )
    (net (code "22") (name "/CIN_22") (class "Default")
      (node (ref "CN7") (pin "4") (pinfunction "4_4") (pintype "passive"))
      (node (ref "P28") (pin "10") (pinfunction "10_10") (pintype "passive"))
      (node (ref "P30") (pin "14") (pinfunction "14_14") (pintype "passive"))
      (node (ref "R75") (pin "1") (pinfunction "1_1") (pintype "passive"))
      (node (ref "R94") (pin "1") (pinfunction "1_1") (pintype "passive"))
    )
    (net (code "23") (name "/CIN_23") (class "Default")
      (node (ref "CN7") (pin "6") (pinfunction "6_6") (pintype "passive"))
      (node (ref "P28") (pin "11") (pinfunction "11_11") (pintype "passive"))
      (node (ref "P30") (pin "15") (pinfunction "15_15") (pintype "passive"))
      (node (ref "R78") (pin "1") (pinfunction "1_1") (pintype "passive"))
      (node (ref "R95") (pin "1") (pinfunction "1_1") (pintype "passive"))
    )
    (net (code "24") (name "/CIN_24") (class "Default")
      (node (ref "CN7") (pin "8") (pinfunction "8_8") (pintype "passive"))
      (node (ref "P28") (pin "12") (pinfunction "12_12") (pintype "passive"))
      (node (ref "P30") (pin "16") (pinfunction "16_16") (pintype "passive"))
      (node (ref "R82") (pin "1") (pinfunction "1_1") (pintype "passive"))
      (node (ref "R96") (pin "1") (pinfunction "1_1") (pintype "passive"))
    )
    (net (code "25") (name "/DCIN_3.3V _RF1") (class "Default")
      (node (ref "CN5") (pin "1") (pinfunction "1_1") (pintype "passive"))
      (node (ref "P1") (pin "1") (pinfunction "1_1") (pintype "passive"))
      (node (ref "R4") (pin "2") (pinfunction "2_2") (pintype "passive"))
    )
    (net (code "26") (name "/DCIN_3.3V _RF2") (class "Default")
      (node (ref "CN5") (pin "3") (pinfunction "3_3") (pintype "passive"))
      (node (ref "P2") (pin "1") (pinfunction "1_1") (pintype "passive"))
      (node (ref "R8") (pin "2") (pinfunction "2_2") (pintype "passive"))
    )
    (net (code "27") (name "/DCIN_3.3V _RF3") (class "Default")
      (node (ref "CN5") (pin "5") (pinfunction "5_5") (pintype "passive"))
      (node (ref "P3") (pin "1") (pinfunction "1_1") (pintype "passive"))
      (node (ref "R11") (pin "2") (pinfunction "2_2") (pintype "passive"))
    )
    (net (code "28") (name "/DCIN_3.3V _RF4") (class "Default")
      (node (ref "CN5") (pin "7") (pinfunction "7_7") (pintype "passive"))
      (node (ref "P4") (pin "1") (pinfunction "1_1") (pintype "passive"))
      (node (ref "R15") (pin "2") (pinfunction "2_2") (pintype "passive"))
    )
    (net (code "29") (name "/DCIN_3.3V _RF5") (class "Default")
      (node (ref "CN5") (pin "9") (pinfunction "9_9") (pintype "passive"))
      (node (ref "P5") (pin "1") (pinfunction "1_1") (pintype "passive"))
      (node (ref "R18") (pin "2") (pinfunction "2_2") (pintype "passive"))
    )
    (net (code "30") (name "/DCIN_3.3V _RF6") (class "Default")
      (node (ref "CN5") (pin "11") (pinfunction "11_11") (pintype "passive"))
      (node (ref "P6") (pin "1") (pinfunction "1_1") (pintype "passive"))
      (node (ref "R22") (pin "2") (pinfunction "2_2") (pintype "passive"))
    )
    (net (code "31") (name "/DCIN_3.3V _RF7") (class "Default")
      (node (ref "CN5") (pin "13") (pinfunction "13_13") (pintype "passive"))
      (node (ref "P7") (pin "1") (pinfunction "1_1") (pintype "passive"))
      (node (ref "R25") (pin "2") (pinfunction "2_2") (pintype "passive"))
    )
    (net (code "32") (name "/DCIN_3.3V _RF8") (class "Default")
      (node (ref "CN5") (pin "15") (pinfunction "15_15") (pintype "passive"))
      (node (ref "P8") (pin "1") (pinfunction "1_1") (pintype "passive"))
      (node (ref "R29") (pin "2") (pinfunction "2_2") (pintype "passive"))
    )
    (net (code "33") (name "/DCIN_3.3V _RF9") (class "Default")
      (node (ref "CN5") (pin "17") (pinfunction "17_17") (pintype "passive"))
      (node (ref "P9") (pin "1") (pinfunction "1_1") (pintype "passive"))
      (node (ref "R32") (pin "2") (pinfunction "2_2") (pintype "passive"))
    )
    (net (code "34") (name "/DCIN_3.3V _RF10") (class "Default")
      (node (ref "CN5") (pin "19") (pinfunction "19_19") (pintype "passive"))
      (node (ref "P10") (pin "1") (pinfunction "1_1") (pintype "passive"))
      (node (ref "R36") (pin "2") (pinfunction "2_2") (pintype "passive"))
    )
    (net (code "35") (name "/DCIN_3.3V _RF11") (class "Default")
      (node (ref "CN5") (pin "21") (pinfunction "21_21") (pintype "passive"))
      (node (ref "P11") (pin "1") (pinfunction "1_1") (pintype "passive"))
      (node (ref "R39") (pin "2") (pinfunction "2_2") (pintype "passive"))
    )
    (net (code "36") (name "/DCIN_3.3V _RF12") (class "Default")
      (node (ref "CN5") (pin "23") (pinfunction "23_23") (pintype "passive"))
      (node (ref "P12") (pin "1") (pinfunction "1_1") (pintype "passive"))
      (node (ref "R43") (pin "2") (pinfunction "2_2") (pintype "passive"))
    )
    (net (code "37") (name "/DCIN_3.3V _RF13") (class "Default")
      (node (ref "CN5") (pin "25") (pinfunction "25_25") (pintype "passive"))
      (node (ref "P13") (pin "1") (pinfunction "1_1") (pintype "passive"))
      (node (ref "R46") (pin "2") (pinfunction "2_2") (pintype "passive"))
    )
    (net (code "38") (name "/DCIN_3.3V _RF14") (class "Default")
      (node (ref "CN5") (pin "27") (pinfunction "27_27") (pintype "passive"))
      (node (ref "P14") (pin "1") (pinfunction "1_1") (pintype "passive"))
      (node (ref "R50") (pin "2") (pinfunction "2_2") (pintype "passive"))
    )
    (net (code "39") (name "/DCIN_3.3V _RF15") (class "Default")
      (node (ref "CN5") (pin "29") (pinfunction "29_29") (pintype "passive"))
      (node (ref "P15") (pin "1") (pinfunction "1_1") (pintype "passive"))
      (node (ref "R53") (pin "2") (pinfunction "2_2") (pintype "passive"))
    )
    (net (code "40") (name "/DCIN_3.3V _RF16") (class "Default")
      (node (ref "CN5") (pin "31") (pinfunction "31_31") (pintype "passive"))
      (node (ref "P16") (pin "1") (pinfunction "1_1") (pintype "passive"))
      (node (ref "R57") (pin "2") (pinfunction "2_2") (pintype "passive"))
    )
    (net (code "41") (name "/DCIN_3.3V _RF17") (class "Default")
      (node (ref "CN5") (pin "33") (pinfunction "33_33") (pintype "passive"))
      (node (ref "P17") (pin "1") (pinfunction "1_1") (pintype "passive"))
      (node (ref "R60") (pin "2") (pinfunction "2_2") (pintype "passive"))
    )
    (net (code "42") (name "/DCIN_3.3V _RF18") (class "Default")
      (node (ref "CN5") (pin "35") (pinfunction "35_35") (pintype "passive"))
      (node (ref "P18") (pin "1") (pinfunction "1_1") (pintype "passive"))
      (node (ref "R64") (pin "2") (pinfunction "2_2") (pintype "passive"))
    )
    (net (code "43") (name "/DCIN_3.3V _RF19") (class "Default")
      (node (ref "CN5") (pin "37") (pinfunction "37_37") (pintype "passive"))
      (node (ref "P19") (pin "1") (pinfunction "1_1") (pintype "passive"))
      (node (ref "R67") (pin "2") (pinfunction "2_2") (pintype "passive"))
    )
    (net (code "44") (name "/DCIN_3.3V _RF20") (class "Default")
      (node (ref "CN5") (pin "39") (pinfunction "39_39") (pintype "passive"))
      (node (ref "P20") (pin "1") (pinfunction "1_1") (pintype "passive"))
      (node (ref "R70") (pin "2") (pinfunction "2_2") (pintype "passive"))
    )
    (net (code "45") (name "/DCIN_3.3V _RF21") (class "Default")
      (node (ref "CN7") (pin "1") (pinfunction "1_1") (pintype "passive"))
      (node (ref "P21") (pin "1") (pinfunction "1_1") (pintype "passive"))
      (node (ref "R72") (pin "2") (pinfunction "2_2") (pintype "passive"))
    )
    (net (code "46") (name "/DCIN_3.3V _RF22") (class "Default")
      (node (ref "CN7") (pin "3") (pinfunction "3_3") (pintype "passive"))
      (node (ref "P22") (pin "1") (pinfunction "1_1") (pintype "passive"))
      (node (ref "R75") (pin "2") (pinfunction "2_2") (pintype "passive"))
    )
    (net (code "47") (name "/DCIN_3.3V _RF23") (class "Default")
      (node (ref "CN7") (pin "5") (pinfunction "5_5") (pintype "passive"))
      (node (ref "P23") (pin "1") (pinfunction "1_1") (pintype "passive"))
      (node (ref "R78") (pin "2") (pinfunction "2_2") (pintype "passive"))
    )
    (net (code "48") (name "/DCIN_3.3V _RF24") (class "Default")
      (node (ref "CN7") (pin "7") (pinfunction "7_7") (pintype "passive"))
      (node (ref "P24") (pin "1") (pinfunction "1_1") (pintype "passive"))
      (node (ref "R82") (pin "2") (pinfunction "2_2") (pintype "passive"))
    )
    (net (code "49") (name "/IN_DCIN_3.3V _RF1") (class "Default")
      (node (ref "CN6") (pin "1") (pinfunction "1_1") (pintype "passive"))
      (node (ref "U3") (pin "49") (pinfunction "49_49") (pintype "passive"))
    )
    (net (code "50") (name "/IN_DCIN_3.3V _RF2") (class "Default")
      (node (ref "CN6") (pin "3") (pinfunction "3_3") (pintype "passive"))
      (node (ref "U3") (pin "43") (pinfunction "43_43") (pintype "passive"))
    )
    (net (code "51") (name "/IN_DCIN_3.3V _RF3") (class "Default")
      (node (ref "CN6") (pin "5") (pinfunction "5_5") (pintype "passive"))
      (node (ref "U3") (pin "37") (pinfunction "37_37") (pintype "passive"))
    )
    (net (code "52") (name "/IN_DCIN_3.3V _RF4") (class "Default")
      (node (ref "CN6") (pin "7") (pinfunction "7_7") (pintype "passive"))
      (node (ref "U3") (pin "31") (pinfunction "31_31") (pintype "passive"))
    )
    (net (code "53") (name "/IN_DCIN_3.3V _RF5") (class "Default")
      (node (ref "CN6") (pin "9") (pinfunction "9_9") (pintype "passive"))
      (node (ref "U3") (pin "23") (pinfunction "23_23") (pintype "passive"))
    )
    (net (code "54") (name "/IN_DCIN_3.3V _RF6") (class "Default")
      (node (ref "CN6") (pin "11") (pinfunction "11_11") (pintype "passive"))
      (node (ref "U3") (pin "17") (pinfunction "17_17") (pintype "passive"))
    )
    (net (code "55") (name "/IN_DCIN_3.3V _RF7") (class "Default")
      (node (ref "CN6") (pin "13") (pinfunction "13_13") (pintype "passive"))
      (node (ref "U3") (pin "11") (pinfunction "11_11") (pintype "passive"))
    )
    (net (code "56") (name "/IN_DCIN_3.3V _RF8") (class "Default")
      (node (ref "CN6") (pin "15") (pinfunction "15_15") (pintype "passive"))
      (node (ref "U3") (pin "5") (pinfunction "5_5") (pintype "passive"))
    )
    (net (code "57") (name "/IN_DCIN_3.3V _RF9") (class "Default")
      (node (ref "CN6") (pin "17") (pinfunction "17_17") (pintype "passive"))
      (node (ref "U2") (pin "49") (pinfunction "49_49") (pintype "passive"))
    )
    (net (code "58") (name "/IN_DCIN_3.3V _RF10") (class "Default")
      (node (ref "CN6") (pin "19") (pinfunction "19_19") (pintype "passive"))
      (node (ref "U2") (pin "43") (pinfunction "43_43") (pintype "passive"))
    )
    (net (code "59") (name "/IN_DCIN_3.3V _RF11") (class "Default")
      (node (ref "CN6") (pin "21") (pinfunction "21_21") (pintype "passive"))
      (node (ref "U2") (pin "37") (pinfunction "37_37") (pintype "passive"))
    )
    (net (code "60") (name "/IN_DCIN_3.3V _RF12") (class "Default")
      (node (ref "CN6") (pin "23") (pinfunction "23_23") (pintype "passive"))
      (node (ref "U2") (pin "31") (pinfunction "31_31") (pintype "passive"))
    )
    (net (code "61") (name "/IN_DCIN_3.3V _RF13") (class "Default")
      (node (ref "CN6") (pin "25") (pinfunction "25_25") (pintype "passive"))
      (node (ref "U2") (pin "23") (pinfunction "23_23") (pintype "passive"))
    )
    (net (code "62") (name "/IN_DCIN_3.3V _RF14") (class "Default")
      (node (ref "CN6") (pin "27") (pinfunction "27_27") (pintype "passive"))
      (node (ref "U2") (pin "17") (pinfunction "17_17") (pintype "passive"))
    )
    (net (code "63") (name "/IN_DCIN_3.3V _RF15") (class "Default")
      (node (ref "CN6") (pin "29") (pinfunction "29_29") (pintype "passive"))
      (node (ref "U2") (pin "11") (pinfunction "11_11") (pintype "passive"))
    )
    (net (code "64") (name "/IN_DCIN_3.3V _RF16") (class "Default")
      (node (ref "CN6") (pin "31") (pinfunction "31_31") (pintype "passive"))
      (node (ref "U2") (pin "5") (pinfunction "5_5") (pintype "passive"))
    )
    (net (code "65") (name "/IN_DCIN_3.3V _RF17") (class "Default")
      (node (ref "CN6") (pin "33") (pinfunction "33_33") (pintype "passive"))
      (node (ref "U1") (pin "49") (pinfunction "49_49") (pintype "passive"))
    )
    (net (code "66") (name "/IN_DCIN_3.3V _RF18") (class "Default")
      (node (ref "CN6") (pin "35") (pinfunction "35_35") (pintype "passive"))
      (node (ref "U1") (pin "43") (pinfunction "43_43") (pintype "passive"))
    )
    (net (code "67") (name "/IN_DCIN_3.3V _RF19") (class "Default")
      (node (ref "CN6") (pin "37") (pinfunction "37_37") (pintype "passive"))
      (node (ref "U1") (pin "37") (pinfunction "37_37") (pintype "passive"))
    )
    (net (code "68") (name "/IN_DCIN_3.3V _RF20") (class "Default")
      (node (ref "CN6") (pin "39") (pinfunction "39_39") (pintype "passive"))
      (node (ref "U1") (pin "31") (pinfunction "31_31") (pintype "passive"))
    )
    (net (code "69") (name "/IN_DCIN_3.3V _RF21") (class "Default")
      (node (ref "P28") (pin "1") (pinfunction "1_1") (pintype "passive"))
      (node (ref "U1") (pin "23") (pinfunction "23_23") (pintype "passive"))
    )
    (net (code "70") (name "/IN_DCIN_3.3V _RF22") (class "Default")
      (node (ref "P28") (pin "2") (pinfunction "2_2") (pintype "passive"))
      (node (ref "U1") (pin "17") (pinfunction "17_17") (pintype "passive"))
    )
    (net (code "71") (name "/IN_DCIN_3.3V _RF23") (class "Default")
      (node (ref "P28") (pin "3") (pinfunction "3_3") (pintype "passive"))
      (node (ref "U1") (pin "11") (pinfunction "11_11") (pintype "passive"))
    )
    (net (code "72") (name "/IN_DCIN_3.3V _RF24") (class "Default")
      (node (ref "P28") (pin "4") (pinfunction "4_4") (pintype "passive"))
      (node (ref "U1") (pin "5") (pinfunction "5_5") (pintype "passive"))
    )
    (net (code "73") (name "/RESET_RF1") (class "Default")
      (node (ref "CN1") (pin "2") (pinfunction "2_2") (pintype "passive"))
      (node (ref "P1") (pin "9") (pinfunction "9_9") (pintype "passive"))
    )
    (net (code "74") (name "/RESET_RF2") (class "Default")
      (node (ref "CN1") (pin "4") (pinfunction "4_4") (pintype "passive"))
      (node (ref "P2") (pin "9") (pinfunction "9_9") (pintype "passive"))
    )
    (net (code "75") (name "/RESET_RF3") (class "Default")
      (node (ref "CN1") (pin "6") (pinfunction "6_6") (pintype "passive"))
      (node (ref "P3") (pin "9") (pinfunction "9_9") (pintype "passive"))
    )
    (net (code "76") (name "/RESET_RF4") (class "Default")
      (node (ref "CN1") (pin "8") (pinfunction "8_8") (pintype "passive"))
      (node (ref "P4") (pin "9") (pinfunction "9_9") (pintype "passive"))
    )
    (net (code "77") (name "/RESET_RF5") (class "Default")
      (node (ref "CN1") (pin "10") (pinfunction "10_10") (pintype "passive"))
      (node (ref "P5") (pin "9") (pinfunction "9_9") (pintype "passive"))
    )
    (net (code "78") (name "/RESET_RF6") (class "Default")
      (node (ref "CN1") (pin "12") (pinfunction "12_12") (pintype "passive"))
      (node (ref "P6") (pin "9") (pinfunction "9_9") (pintype "passive"))
    )
    (net (code "79") (name "/RESET_RF7") (class "Default")
      (node (ref "CN1") (pin "14") (pinfunction "14_14") (pintype "passive"))
      (node (ref "P7") (pin "9") (pinfunction "9_9") (pintype "passive"))
    )
    (net (code "80") (name "/RESET_RF8") (class "Default")
      (node (ref "CN1") (pin "16") (pinfunction "16_16") (pintype "passive"))
      (node (ref "P8") (pin "9") (pinfunction "9_9") (pintype "passive"))
    )
    (net (code "81") (name "/RESET_RF9") (class "Default")
      (node (ref "CN1") (pin "18") (pinfunction "18_18") (pintype "passive"))
      (node (ref "P9") (pin "9") (pinfunction "9_9") (pintype "passive"))
    )
    (net (code "82") (name "/RESET_RF10") (class "Default")
      (node (ref "CN1") (pin "20") (pinfunction "20_20") (pintype "passive"))
      (node (ref "P10") (pin "9") (pinfunction "9_9") (pintype "passive"))
    )
    (net (code "83") (name "/RESET_RF11") (class "Default")
      (node (ref "CN1") (pin "22") (pinfunction "22_22") (pintype "passive"))
      (node (ref "P11") (pin "9") (pinfunction "9_9") (pintype "passive"))
    )
    (net (code "84") (name "/RESET_RF12") (class "Default")
      (node (ref "CN1") (pin "24") (pinfunction "24_24") (pintype "passive"))
      (node (ref "P12") (pin "9") (pinfunction "9_9") (pintype "passive"))
    )
    (net (code "85") (name "/RESET_RF13") (class "Default")
      (node (ref "CN1") (pin "26") (pinfunction "26_26") (pintype "passive"))
      (node (ref "P13") (pin "9") (pinfunction "9_9") (pintype "passive"))
    )
    (net (code "86") (name "/RESET_RF14") (class "Default")
      (node (ref "CN1") (pin "28") (pinfunction "28_28") (pintype "passive"))
      (node (ref "P14") (pin "9") (pinfunction "9_9") (pintype "passive"))
    )
    (net (code "87") (name "/RESET_RF15") (class "Default")
      (node (ref "CN1") (pin "30") (pinfunction "30_30") (pintype "passive"))
      (node (ref "P15") (pin "9") (pinfunction "9_9") (pintype "passive"))
    )
    (net (code "88") (name "/RESET_RF16") (class "Default")
      (node (ref "CN1") (pin "32") (pinfunction "32_32") (pintype "passive"))
      (node (ref "P16") (pin "9") (pinfunction "9_9") (pintype "passive"))
    )
    (net (code "89") (name "/RESET_RF17") (class "Default")
      (node (ref "CN1") (pin "34") (pinfunction "34_34") (pintype "passive"))
      (node (ref "P17") (pin "9") (pinfunction "9_9") (pintype "passive"))
    )
    (net (code "90") (name "/RESET_RF18") (class "Default")
      (node (ref "CN1") (pin "36") (pinfunction "36_36") (pintype "passive"))
      (node (ref "P18") (pin "9") (pinfunction "9_9") (pintype "passive"))
    )
    (net (code "91") (name "/RESET_RF19") (class "Default")
      (node (ref "CN1") (pin "38") (pinfunction "38_38") (pintype "passive"))
      (node (ref "P19") (pin "9") (pinfunction "9_9") (pintype "passive"))
    )
    (net (code "92") (name "/RESET_RF20") (class "Default")
      (node (ref "CN1") (pin "40") (pinfunction "40_40") (pintype "passive"))
      (node (ref "P20") (pin "9") (pinfunction "9_9") (pintype "passive"))
    )
    (net (code "93") (name "/RESET_RF21") (class "Default")
      (node (ref "P21") (pin "9") (pinfunction "9_9") (pintype "passive"))
      (node (ref "P26") (pin "1") (pinfunction "1_1") (pintype "passive"))
    )
    (net (code "94") (name "/RESET_RF22") (class "Default")
      (node (ref "P22") (pin "9") (pinfunction "9_9") (pintype "passive"))
      (node (ref "P26") (pin "2") (pinfunction "2_2") (pintype "passive"))
    )
    (net (code "95") (name "/RESET_RF23") (class "Default")
      (node (ref "P23") (pin "9") (pinfunction "9_9") (pintype "passive"))
      (node (ref "P26") (pin "3") (pinfunction "3_3") (pintype "passive"))
    )
    (net (code "96") (name "/RESET_RF24") (class "Default")
      (node (ref "P24") (pin "9") (pinfunction "9_9") (pintype "passive"))
      (node (ref "P26") (pin "4") (pinfunction "4_4") (pintype "passive"))
    )
    (net (code "102") (name "/RXD0_RF1") (class "Default")
      (node (ref "P1") (pin "5") (pinfunction "5_5") (pintype "passive"))
      (node (ref "U3") (pin "48") (pinfunction "48_48") (pintype "passive"))
    )
    (net (code "103") (name "/RXD0_RF2") (class "Default")
      (node (ref "P2") (pin "5") (pinfunction "5_5") (pintype "passive"))
      (node (ref "U3") (pin "42") (pinfunction "42_42") (pintype "passive"))
    )
    (net (code "104") (name "/RXD0_RF3") (class "Default")
      (node (ref "P3") (pin "5") (pinfunction "5_5") (pintype "passive"))
      (node (ref "U3") (pin "36") (pinfunction "36_36") (pintype "passive"))
    )
    (net (code "105") (name "/RXD0_RF4") (class "Default")
      (node (ref "P4") (pin "5") (pinfunction "5_5") (pintype "passive"))
      (node (ref "U3") (pin "30") (pinfunction "30_30") (pintype "passive"))
    )
    (net (code "106") (name "/RXD0_RF5") (class "Default")
      (node (ref "P5") (pin "5") (pinfunction "5_5") (pintype "passive"))
      (node (ref "U3") (pin "22") (pinfunction "22_22") (pintype "passive"))
    )
    (net (code "107") (name "/RXD0_RF6") (class "Default")
      (node (ref "P6") (pin "5") (pinfunction "5_5") (pintype "passive"))
      (node (ref "U3") (pin "16") (pinfunction "16_16") (pintype "passive"))
    )
    (net (code "108") (name "/RXD0_RF7") (class "Default")
      (node (ref "P7") (pin "5") (pinfunction "5_5") (pintype "passive"))
      (node (ref "U3") (pin "10") (pinfunction "10_10") (pintype "passive"))
    )
    (net (code "109") (name "/RXD0_RF8") (class "Default")
      (node (ref "P8") (pin "5") (pinfunction "5_5") (pintype "passive"))
      (node (ref "U3") (pin "4") (pinfunction "4_4") (pintype "passive"))
    )
    (net (code "110") (name "/RXD0_RF9") (class "Default")
      (node (ref "P9") (pin "5") (pinfunction "5_5") (pintype "passive"))
      (node (ref "U2") (pin "48") (pinfunction "48_48") (pintype "passive"))
    )
    (net (code "111") (name "/RXD0_RF10") (class "Default")
      (node (ref "P10") (pin "5") (pinfunction "5_5") (pintype "passive"))
      (node (ref "U2") (pin "42") (pinfunction "42_42") (pintype "passive"))
    )
    (net (code "112") (name "/RXD0_RF11") (class "Default")
      (node (ref "P11") (pin "5") (pinfunction "5_5") (pintype "passive"))
      (node (ref "U2") (pin "36") (pinfunction "36_36") (pintype "passive"))
    )
    (net (code "113") (name "/RXD0_RF12") (class "Default")
      (node (ref "P12") (pin "5") (pinfunction "5_5") (pintype "passive"))
      (node (ref "U2") (pin "30") (pinfunction "30_30") (pintype "passive"))
    )
    (net (code "114") (name "/RXD0_RF13") (class "Default")
      (node (ref "P13") (pin "5") (pinfunction "5_5") (pintype "passive"))
      (node (ref "U2") (pin "22") (pinfunction "22_22") (pintype "passive"))
    )
    (net (code "115") (name "/RXD0_RF14") (class "Default")
      (node (ref "P14") (pin "5") (pinfunction "5_5") (pintype "passive"))
      (node (ref "U2") (pin "16") (pinfunction "16_16") (pintype "passive"))
    )
    (net (code "116") (name "/RXD0_RF15") (class "Default")
      (node (ref "P15") (pin "5") (pinfunction "5_5") (pintype "passive"))
      (node (ref "U2") (pin "10") (pinfunction "10_10") (pintype "passive"))
    )
    (net (code "117") (name "/RXD0_RF16") (class "Default")
      (node (ref "P16") (pin "5") (pinfunction "5_5") (pintype "passive"))
      (node (ref "U2") (pin "4") (pinfunction "4_4") (pintype "passive"))
    )
    (net (code "118") (name "/RXD0_RF17") (class "Default")
      (node (ref "P17") (pin "5") (pinfunction "5_5") (pintype "passive"))
      (node (ref "U1") (pin "48") (pinfunction "48_48") (pintype "passive"))
    )
    (net (code "119") (name "/RXD0_RF18") (class "Default")
      (node (ref "P18") (pin "5") (pinfunction "5_5") (pintype "passive"))
      (node (ref "U1") (pin "42") (pinfunction "42_42") (pintype "passive"))
    )
    (net (code "120") (name "/RXD0_RF19") (class "Default")
      (node (ref "P19") (pin "5") (pinfunction "5_5") (pintype "passive"))
      (node (ref "U1") (pin "36") (pinfunction "36_36") (pintype "passive"))
    )
    (net (code "121") (name "/RXD0_RF20") (class "Default")
      (node (ref "P20") (pin "5") (pinfunction "5_5") (pintype "passive"))
      (node (ref "U1") (pin "30") (pinfunction "30_30") (pintype "passive"))
    )
    (net (code "122") (name "/RXD0_RF21") (class "Default")
      (node (ref "P21") (pin "5") (pinfunction "5_5") (pintype "passive"))
      (node (ref "U1") (pin "22") (pinfunction "22_22") (pintype "passive"))
    )
    (net (code "123") (name "/RXD0_RF22") (class "Default")
      (node (ref "P22") (pin "5") (pinfunction "5_5") (pintype "passive"))
      (node (ref "U1") (pin "16") (pinfunction "16_16") (pintype "passive"))
    )
    (net (code "124") (name "/RXD0_RF23") (class "Default")
      (node (ref "P23") (pin "5") (pinfunction "5_5") (pintype "passive"))
      (node (ref "U1") (pin "10") (pinfunction "10_10") (pintype "passive"))
    )
    (net (code "125") (name "/RXD0_RF24") (class "Default")
      (node (ref "P24") (pin "5") (pinfunction "5_5") (pintype "passive"))
      (node (ref "U1") (pin "4") (pinfunction "4_4") (pintype "passive"))
    )
    (net (code "126") (name "/TXD0_RF1") (class "Default")
      (node (ref "P1") (pin "6") (pinfunction "6_6") (pintype "passive"))
      (node (ref "U3") (pin "46") (pinfunction "46_46") (pintype "passive"))
    )
    (net (code "127") (name "/TXD0_RF2") (class "Default")
      (node (ref "P2") (pin "6") (pinfunction "6_6") (pintype "passive"))
      (node (ref "U3") (pin "40") (pinfunction "40_40") (pintype "passive"))
    )
    (net (code "128") (name "/TXD0_RF3") (class "Default")
      (node (ref "P3") (pin "6") (pinfunction "6_6") (pintype "passive"))
      (node (ref "U3") (pin "34") (pinfunction "34_34") (pintype "passive"))
    )
    (net (code "129") (name "/TXD0_RF4") (class "Default")
      (node (ref "P4") (pin "6") (pinfunction "6_6") (pintype "passive"))
      (node (ref "U3") (pin "28") (pinfunction "28_28") (pintype "passive"))
    )
    (net (code "130") (name "/TXD0_RF5") (class "Default")
      (node (ref "P5") (pin "6") (pinfunction "6_6") (pintype "passive"))
      (node (ref "U3") (pin "20") (pinfunction "20_20") (pintype "passive"))
    )
    (net (code "131") (name "/TXD0_RF6") (class "Default")
      (node (ref "P6") (pin "6") (pinfunction "6_6") (pintype "passive"))
      (node (ref "U3") (pin "14") (pinfunction "14_14") (pintype "passive"))
    )
    (net (code "132") (name "/TXD0_RF7") (class "Default")
      (node (ref "P7") (pin "6") (pinfunction "6_6") (pintype "passive"))
      (node (ref "U3") (pin "8") (pinfunction "8_8") (pintype "passive"))
    )
    (net (code "133") (name "/TXD0_RF8") (class "Default")
      (node (ref "P8") (pin "6") (pinfunction "6_6") (pintype "passive"))
      (node (ref "U3") (pin "2") (pinfunction "2_2") (pintype "passive"))
    )
    (net (code "134") (name "/TXD0_RF9") (class "Default")
      (node (ref "P9") (pin "6") (pinfunction "6_6") (pintype "passive"))
      (node (ref "U2") (pin "46") (pinfunction "46_46") (pintype "passive"))
    )
    (net (code "135") (name "/TXD0_RF10") (class "Default")
      (node (ref "P10") (pin "6") (pinfunction "6_6") (pintype "passive"))
      (node (ref "U2") (pin "40") (pinfunction "40_40") (pintype "passive"))
    )
    (net (code "136") (name "/TXD0_RF11") (class "Default")
      (node (ref "P11") (pin "6") (pinfunction "6_6") (pintype "passive"))
      (node (ref "U2") (pin "34") (pinfunction "34_34") (pintype "passive"))
    )
    (net (code "137") (name "/TXD0_RF12") (class "Default")
      (node (ref "P12") (pin "6") (pinfunction "6_6") (pintype "passive"))
      (node (ref "U2") (pin "28") (pinfunction "28_28") (pintype "passive"))
    )
    (net (code "138") (name "/TXD0_RF13") (class "Default")
      (node (ref "P13") (pin "6") (pinfunction "6_6") (pintype "passive"))
      (node (ref "U2") (pin "20") (pinfunction "20_20") (pintype "passive"))
    )
    (net (code "139") (name "/TXD0_RF14") (class "Default")
      (node (ref "P14") (pin "6") (pinfunction "6_6") (pintype "passive"))
      (node (ref "U2") (pin "14") (pinfunction "14_14") (pintype "passive"))
    )
    (net (code "140") (name "/TXD0_RF15") (class "Default")
      (node (ref "P15") (pin "6") (pinfunction "6_6") (pintype "passive"))
      (node (ref "U2") (pin "8") (pinfunction "8_8") (pintype "passive"))
    )
    (net (code "141") (name "/TXD0_RF16") (class "Default")
      (node (ref "P16") (pin "6") (pinfunction "6_6") (pintype "passive"))
      (node (ref "U2") (pin "2") (pinfunction "2_2") (pintype "passive"))
    )
    (net (code "142") (name "/TXD0_RF17") (class "Default")
      (node (ref "P17") (pin "6") (pinfunction "6_6") (pintype "passive"))
      (node (ref "U1") (pin "46") (pinfunction "46_46") (pintype "passive"))
    )
    (net (code "143") (name "/TXD0_RF18") (class "Default")
      (node (ref "P18") (pin "6") (pinfunction "6_6") (pintype "passive"))
      (node (ref "U1") (pin "40") (pinfunction "40_40") (pintype "passive"))
    )
    (net (code "144") (name "/TXD0_RF19") (class "Default")
      (node (ref "P19") (pin "6") (pinfunction "6_6") (pintype "passive"))
      (node (ref "U1") (pin "34") (pinfunction "34_34") (pintype "passive"))
    )
    (net (code "145") (name "/TXD0_RF20") (class "Default")
      (node (ref "P20") (pin "6") (pinfunction "6_6") (pintype "passive"))
      (node (ref "U1") (pin "28") (pinfunction "28_28") (pintype "passive"))
    )
    (net (code "146") (name "/TXD0_RF21") (class "Default")
      (node (ref "P21") (pin "6") (pinfunction "6_6") (pintype "passive"))
      (node (ref "U1") (pin "20") (pinfunction "20_20") (pintype "passive"))
    )
    (net (code "147") (name "/TXD0_RF22") (class "Default")
      (node (ref "P22") (pin "6") (pinfunction "6_6") (pintype "passive"))
      (node (ref "U1") (pin "14") (pinfunction "14_14") (pintype "passive"))
    )
    (net (code "148") (name "/TXD0_RF23") (class "Default")
      (node (ref "P23") (pin "6") (pinfunction "6_6") (pintype "passive"))
      (node (ref "U1") (pin "8") (pinfunction "8_8") (pintype "passive"))
    )
    (net (code "149") (name "/TXD0_RF24") (class "Default")
      (node (ref "P24") (pin "6") (pinfunction "6_6") (pintype "passive"))
      (node (ref "U1") (pin "2") (pinfunction "2_2") (pintype "passive"))
    )
    (net (code "150") (name "/VBAT_RF1") (class "Default")
      (node (ref "CN7") (pin "9") (pinfunction "9_9") (pintype "passive"))
      (node (ref "P1") (pin "2") (pinfunction "2_2") (pintype "passive"))
      (node (ref "R5") (pin "2") (pinfunction "2_2") (pintype "passive"))
    )
    (net (code "151") (name "/VBAT_RF2") (class "Default")
      (node (ref "CN7") (pin "11") (pinfunction "11_11") (pintype "passive"))
      (node (ref "P2") (pin "2") (pinfunction "2_2") (pintype "passive"))
      (node (ref "R12") (pin "2") (pinfunction "2_2") (pintype "passive"))
    )
    (net (code "152") (name "/VBAT_RF3") (class "Default")
      (node (ref "CN7") (pin "13") (pinfunction "13_13") (pintype "passive"))
      (node (ref "P3") (pin "2") (pinfunction "2_2") (pintype "passive"))
      (node (ref "R19") (pin "2") (pinfunction "2_2") (pintype "passive"))
    )
    (net (code "153") (name "/VBAT_RF4") (class "Default")
      (node (ref "CN7") (pin "15") (pinfunction "15_15") (pintype "passive"))
      (node (ref "P4") (pin "2") (pinfunction "2_2") (pintype "passive"))
      (node (ref "R26") (pin "2") (pinfunction "2_2") (pintype "passive"))
    )
    (net (code "154") (name "/VBAT_RF5") (class "Default")
      (node (ref "CN7") (pin "17") (pinfunction "17_17") (pintype "passive"))
      (node (ref "P5") (pin "2") (pinfunction "2_2") (pintype "passive"))
      (node (ref "R33") (pin "2") (pinfunction "2_2") (pintype "passive"))
    )
    (net (code "155") (name "/VBAT_RF6") (class "Default")
      (node (ref "CN7") (pin "19") (pinfunction "19_19") (pintype "passive"))
      (node (ref "P6") (pin "2") (pinfunction "2_2") (pintype "passive"))
      (node (ref "R40") (pin "2") (pinfunction "2_2") (pintype "passive"))
    )
    (net (code "156") (name "/VBAT_RF7") (class "Default")
      (node (ref "CN7") (pin "21") (pinfunction "21_21") (pintype "passive"))
      (node (ref "P7") (pin "2") (pinfunction "2_2") (pintype "passive"))
      (node (ref "R47") (pin "2") (pinfunction "2_2") (pintype "passive"))
    )
    (net (code "157") (name "/VBAT_RF8") (class "Default")
      (node (ref "CN7") (pin "23") (pinfunction "23_23") (pintype "passive"))
      (node (ref "P8") (pin "2") (pinfunction "2_2") (pintype "passive"))
      (node (ref "R54") (pin "2") (pinfunction "2_2") (pintype "passive"))
    )
    (net (code "158") (name "/VBAT_RF9") (class "Default")
      (node (ref "CN7") (pin "25") (pinfunction "25_25") (pintype "passive"))
      (node (ref "P9") (pin "2") (pinfunction "2_2") (pintype "passive"))
      (node (ref "R61") (pin "2") (pinfunction "2_2") (pintype "passive"))
    )
    (net (code "159") (name "/VBAT_RF10") (class "Default")
      (node (ref "CN7") (pin "27") (pinfunction "27_27") (pintype "passive"))
      (node (ref "P10") (pin "2") (pinfunction "2_2") (pintype "passive"))
      (node (ref "R68") (pin "2") (pinfunction "2_2") (pintype "passive"))
    )
    (net (code "160") (name "/VBAT_RF11") (class "Default")
      (node (ref "CN7") (pin "29") (pinfunction "29_29") (pintype "passive"))
      (node (ref "P11") (pin "2") (pinfunction "2_2") (pintype "passive"))
      (node (ref "R79") (pin "2") (pinfunction "2_2") (pintype "passive"))
    )
    (net (code "161") (name "/VBAT_RF12") (class "Default")
      (node (ref "CN7") (pin "31") (pinfunction "31_31") (pintype "passive"))
      (node (ref "P12") (pin "2") (pinfunction "2_2") (pintype "passive"))
      (node (ref "R84") (pin "2") (pinfunction "2_2") (pintype "passive"))
    )
    (net (code "162") (name "/VBAT_RF13") (class "Default")
      (node (ref "CN7") (pin "33") (pinfunction "33_33") (pintype "passive"))
      (node (ref "P13") (pin "2") (pinfunction "2_2") (pintype "passive"))
      (node (ref "R85") (pin "2") (pinfunction "2_2") (pintype "passive"))
    )
    (net (code "163") (name "/VBAT_RF14") (class "Default")
      (node (ref "CN7") (pin "35") (pinfunction "35_35") (pintype "passive"))
      (node (ref "P14") (pin "2") (pinfunction "2_2") (pintype "passive"))
      (node (ref "R86") (pin "2") (pinfunction "2_2") (pintype "passive"))
    )
    (net (code "164") (name "/VBAT_RF15") (class "Default")
      (node (ref "CN7") (pin "37") (pinfunction "37_37") (pintype "passive"))
      (node (ref "P15") (pin "2") (pinfunction "2_2") (pintype "passive"))
      (node (ref "R87") (pin "2") (pinfunction "2_2") (pintype "passive"))
    )
    (net (code "165") (name "/VBAT_RF16") (class "Default")
      (node (ref "CN7") (pin "39") (pinfunction "39_39") (pintype "passive"))
      (node (ref "P16") (pin "2") (pinfunction "2_2") (pintype "passive"))
      (node (ref "R88") (pin "2") (pinfunction "2_2") (pintype "passive"))
    )
    (net (code "166") (name "/VBAT_RF17") (class "Default")
      (node (ref "P17") (pin "2") (pinfunction "2_2") (pintype "passive"))
      (node (ref "P30") (pin "1") (pinfunction "1_1") (pintype "passive"))
      (node (ref "R89") (pin "2") (pinfunction "2_2") (pintype "passive"))
    )
    (net (code "167") (name "/VBAT_RF18") (class "Default")
      (node (ref "P18") (pin "2") (pinfunction "2_2") (pintype "passive"))
      (node (ref "P30") (pin "2") (pinfunction "2_2") (pintype "passive"))
      (node (ref "R90") (pin "2") (pinfunction "2_2") (pintype "passive"))
    )
    (net (code "168") (name "/VBAT_RF19") (class "Default")
      (node (ref "P19") (pin "2") (pinfunction "2_2") (pintype "passive"))
      (node (ref "P30") (pin "3") (pinfunction "3_3") (pintype "passive"))
      (node (ref "R91") (pin "2") (pinfunction "2_2") (pintype "passive"))
    )
    (net (code "169") (name "/VBAT_RF20") (class "Default")
      (node (ref "P20") (pin "2") (pinfunction "2_2") (pintype "passive"))
      (node (ref "P30") (pin "4") (pinfunction "4_4") (pintype "passive"))
      (node (ref "R92") (pin "2") (pinfunction "2_2") (pintype "passive"))
    )
    (net (code "170") (name "/VBAT_RF21") (class "Default")
      (node (ref "P21") (pin "2") (pinfunction "2_2") (pintype "passive"))
      (node (ref "P30") (pin "5") (pinfunction "5_5") (pintype "passive"))
      (node (ref "R93") (pin "2") (pinfunction "2_2") (pintype "passive"))
    )
    (net (code "171") (name "/VBAT_RF22") (class "Default")
      (node (ref "P22") (pin "2") (pinfunction "2_2") (pintype "passive"))
      (node (ref "P30") (pin "6") (pinfunction "6_6") (pintype "passive"))
      (node (ref "R94") (pin "2") (pinfunction "2_2") (pintype "passive"))
    )
    (net (code "172") (name "/VBAT_RF23") (class "Default")
      (node (ref "P23") (pin "2") (pinfunction "2_2") (pintype "passive"))
      (node (ref "P30") (pin "7") (pinfunction "7_7") (pintype "passive"))
      (node (ref "R95") (pin "2") (pinfunction "2_2") (pintype "passive"))
    )
    (net (code "173") (name "/VBAT_RF24") (class "Default")
      (node (ref "P24") (pin "2") (pinfunction "2_2") (pintype "passive"))
      (node (ref "P30") (pin "8") (pinfunction "8_8") (pintype "passive"))
      (node (ref "R96") (pin "2") (pinfunction "2_2") (pintype "passive"))
    )
    (net (code "174") (name "/VCC_RF_RF1") (class "Default")
      (node (ref "CN2") (pin "1") (pinfunction "1_1") (pintype "passive"))
      (node (ref "CN3") (pin "2") (pinfunction "2_2") (pintype "passive"))
      (node (ref "CN4") (pin "2") (pinfunction "2_2") (pintype "passive"))
      (node (ref "P1") (pin "10") (pinfunction "10_10") (pintype "passive"))
    )
    (net (code "175") (name "/VCC_RF_RF2") (class "Default")
      (node (ref "CN2") (pin "3") (pinfunction "3_3") (pintype "passive"))
      (node (ref "CN3") (pin "4") (pinfunction "4_4") (pintype "passive"))
      (node (ref "CN4") (pin "4") (pinfunction "4_4") (pintype "passive"))
      (node (ref "P2") (pin "10") (pinfunction "10_10") (pintype "passive"))
    )
    (net (code "176") (name "/VCC_RF_RF3") (class "Default")
      (node (ref "CN2") (pin "5") (pinfunction "5_5") (pintype "passive"))
      (node (ref "CN3") (pin "6") (pinfunction "6_6") (pintype "passive"))
      (node (ref "CN4") (pin "6") (pinfunction "6_6") (pintype "passive"))
      (node (ref "P3") (pin "10") (pinfunction "10_10") (pintype "passive"))
    )
    (net (code "177") (name "/VCC_RF_RF4") (class "Default")
      (node (ref "CN2") (pin "7") (pinfunction "7_7") (pintype "passive"))
      (node (ref "CN3") (pin "8") (pinfunction "8_8") (pintype "passive"))
      (node (ref "CN4") (pin "8") (pinfunction "8_8") (pintype "passive"))
      (node (ref "P4") (pin "10") (pinfunction "10_10") (pintype "passive"))
    )
    (net (code "178") (name "/VCC_RF_RF5") (class "Default")
      (node (ref "CN2") (pin "9") (pinfunction "9_9") (pintype "passive"))
      (node (ref "CN3") (pin "10") (pinfunction "10_10") (pintype "passive"))
      (node (ref "CN4") (pin "10") (pinfunction "10_10") (pintype "passive"))
      (node (ref "P5") (pin "10") (pinfunction "10_10") (pintype "passive"))
    )
    (net (code "179") (name "/VCC_RF_RF6") (class "Default")
      (node (ref "CN2") (pin "11") (pinfunction "11_11") (pintype "passive"))
      (node (ref "CN3") (pin "12") (pinfunction "12_12") (pintype "passive"))
      (node (ref "CN4") (pin "12") (pinfunction "12_12") (pintype "passive"))
      (node (ref "P6") (pin "10") (pinfunction "10_10") (pintype "passive"))
    )
    (net (code "180") (name "/VCC_RF_RF7") (class "Default")
      (node (ref "CN2") (pin "13") (pinfunction "13_13") (pintype "passive"))
      (node (ref "CN3") (pin "14") (pinfunction "14_14") (pintype "passive"))
      (node (ref "CN4") (pin "14") (pinfunction "14_14") (pintype "passive"))
      (node (ref "P7") (pin "10") (pinfunction "10_10") (pintype "passive"))
    )
    (net (code "181") (name "/VCC_RF_RF8") (class "Default")
      (node (ref "CN2") (pin "15") (pinfunction "15_15") (pintype "passive"))
      (node (ref "CN3") (pin "16") (pinfunction "16_16") (pintype "passive"))
      (node (ref "CN4") (pin "16") (pinfunction "16_16") (pintype "passive"))
      (node (ref "P8") (pin "10") (pinfunction "10_10") (pintype "passive"))
    )
    (net (code "182") (name "/VCC_RF_RF9") (class "Default")
      (node (ref "CN2") (pin "17") (pinfunction "17_17") (pintype "passive"))
      (node (ref "CN3") (pin "18") (pinfunction "18_18") (pintype "passive"))
      (node (ref "CN4") (pin "18") (pinfunction "18_18") (pintype "passive"))
      (node (ref "P9") (pin "10") (pinfunction "10_10") (pintype "passive"))
    )
    (net (code "183") (name "/VCC_RF_RF10") (class "Default")
      (node (ref "CN2") (pin "19") (pinfunction "19_19") (pintype "passive"))
      (node (ref "CN3") (pin "20") (pinfunction "20_20") (pintype "passive"))
      (node (ref "CN4") (pin "20") (pinfunction "20_20") (pintype "passive"))
      (node (ref "P10") (pin "10") (pinfunction "10_10") (pintype "passive"))
    )
    (net (code "184") (name "/VCC_RF_RF11") (class "Default")
      (node (ref "CN2") (pin "21") (pinfunction "21_21") (pintype "passive"))
      (node (ref "CN3") (pin "22") (pinfunction "22_22") (pintype "passive"))
      (node (ref "CN4") (pin "22") (pinfunction "22_22") (pintype "passive"))
      (node (ref "P11") (pin "10") (pinfunction "10_10") (pintype "passive"))
    )
    (net (code "185") (name "/VCC_RF_RF12") (class "Default")
      (node (ref "CN2") (pin "23") (pinfunction "23_23") (pintype "passive"))
      (node (ref "CN3") (pin "24") (pinfunction "24_24") (pintype "passive"))
      (node (ref "CN4") (pin "24") (pinfunction "24_24") (pintype "passive"))
      (node (ref "P12") (pin "10") (pinfunction "10_10") (pintype "passive"))
    )
    (net (code "186") (name "/VCC_RF_RF13") (class "Default")
      (node (ref "CN2") (pin "25") (pinfunction "25_25") (pintype "passive"))
      (node (ref "CN3") (pin "26") (pinfunction "26_26") (pintype "passive"))
      (node (ref "CN4") (pin "26") (pinfunction "26_26") (pintype "passive"))
      (node (ref "P13") (pin "10") (pinfunction "10_10") (pintype "passive"))
    )
    (net (code "187") (name "/VCC_RF_RF14") (class "Default")
      (node (ref "CN2") (pin "27") (pinfunction "27_27") (pintype "passive"))
      (node (ref "CN3") (pin "28") (pinfunction "28_28") (pintype "passive"))
      (node (ref "CN4") (pin "28") (pinfunction "28_28") (pintype "passive"))
      (node (ref "P14") (pin "10") (pinfunction "10_10") (pintype "passive"))
    )
    (net (code "188") (name "/VCC_RF_RF15") (class "Default")
      (node (ref "CN2") (pin "29") (pinfunction "29_29") (pintype "passive"))
      (node (ref "CN3") (pin "30") (pinfunction "30_30") (pintype "passive"))
      (node (ref "CN4") (pin "30") (pinfunction "30_30") (pintype "passive"))
      (node (ref "P15") (pin "10") (pinfunction "10_10") (pintype "passive"))
    )
    (net (code "189") (name "/VCC_RF_RF16") (class "Default")
      (node (ref "CN2") (pin "31") (pinfunction "31_31") (pintype "passive"))
      (node (ref "CN3") (pin "32") (pinfunction "32_32") (pintype "passive"))
      (node (ref "CN4") (pin "32") (pinfunction "32_32") (pintype "passive"))
      (node (ref "P16") (pin "10") (pinfunction "10_10") (pintype "passive"))
    )
    (net (code "190") (name "/VCC_RF_RF17") (class "Default")
      (node (ref "CN2") (pin "33") (pinfunction "33_33") (pintype "passive"))
      (node (ref "CN3") (pin "34") (pinfunction "34_34") (pintype "passive"))
      (node (ref "CN4") (pin "34") (pinfunction "34_34") (pintype "passive"))
      (node (ref "P17") (pin "10") (pinfunction "10_10") (pintype "passive"))
    )
    (net (code "191") (name "/VCC_RF_RF18") (class "Default")
      (node (ref "CN2") (pin "35") (pinfunction "35_35") (pintype "passive"))
      (node (ref "CN3") (pin "36") (pinfunction "36_36") (pintype "passive"))
      (node (ref "CN4") (pin "36") (pinfunction "36_36") (pintype "passive"))
      (node (ref "P18") (pin "10") (pinfunction "10_10") (pintype "passive"))
    )
    (net (code "192") (name "/VCC_RF_RF19") (class "Default")
      (node (ref "CN2") (pin "37") (pinfunction "37_37") (pintype "passive"))
      (node (ref "CN3") (pin "38") (pinfunction "38_38") (pintype "passive"))
      (node (ref "CN4") (pin "38") (pinfunction "38_38") (pintype "passive"))
      (node (ref "P19") (pin "10") (pinfunction "10_10") (pintype "passive"))
    )
    (net (code "193") (name "/VCC_RF_RF20") (class "Default")
      (node (ref "CN2") (pin "39") (pinfunction "39_39") (pintype "passive"))
      (node (ref "CN3") (pin "40") (pinfunction "40_40") (pintype "passive"))
      (node (ref "CN4") (pin "40") (pinfunction "40_40") (pintype "passive"))
      (node (ref "P20") (pin "10") (pinfunction "10_10") (pintype "passive"))
    )
    (net (code "194") (name "/VCC_RF_RF21") (class "Default")
      (node (ref "P21") (pin "10") (pinfunction "10_10") (pintype "passive"))
      (node (ref "P25") (pin "1") (pinfunction "1_1") (pintype "passive"))
      (node (ref "P27") (pin "1") (pinfunction "1_1") (pintype "passive"))
      (node (ref "P29") (pin "1") (pinfunction "1_1") (pintype "passive"))
    )
    (net (code "195") (name "/VCC_RF_RF22") (class "Default")
      (node (ref "P22") (pin "10") (pinfunction "10_10") (pintype "passive"))
      (node (ref "P25") (pin "2") (pinfunction "2_2") (pintype "passive"))
      (node (ref "P27") (pin "2") (pinfunction "2_2") (pintype "passive"))
      (node (ref "P29") (pin "2") (pinfunction "2_2") (pintype "passive"))
    )
    (net (code "196") (name "/VCC_RF_RF23") (class "Default")
      (node (ref "P23") (pin "10") (pinfunction "10_10") (pintype "passive"))
      (node (ref "P25") (pin "3") (pinfunction "3_3") (pintype "passive"))
      (node (ref "P27") (pin "3") (pinfunction "3_3") (pintype "passive"))
      (node (ref "P29") (pin "3") (pinfunction "3_3") (pintype "passive"))
    )
    (net (code "197") (name "/VCC_RF_RF24") (class "Default")
      (node (ref "P24") (pin "10") (pinfunction "10_10") (pintype "passive"))
      (node (ref "P25") (pin "4") (pinfunction "4_4") (pintype "passive"))
      (node (ref "P27") (pin "4") (pinfunction "4_4") (pintype "passive"))
      (node (ref "P29") (pin "4") (pinfunction "4_4") (pintype "passive"))
    )
    (net (code "198") (name "GND_RF1") (class "Default")
      (node (ref "CN1") (pin "1") (pinfunction "1_1") (pintype "passive"))
      (node (ref "CN2") (pin "2") (pinfunction "2_2") (pintype "passive"))
      (node (ref "P1") (pin "13") (pinfunction "13_13") (pintype "passive"))
      (node (ref "P1") (pin "14") (pinfunction "14_14") (pintype "passive"))
      (node (ref "P1") (pin "15") (pinfunction "15_15") (pintype "passive"))
      (node (ref "R1") (pin "1") (pinfunction "1_1") (pintype "passive"))
      (node (ref "R2") (pin "1") (pinfunction "1_1") (pintype "passive"))
      (node (ref "U3") (pin "50") (pinfunction "50_50") (pintype "passive"))
    )
    (net (code "199") (name "GND_RF2") (class "Default")
      (node (ref "CN1") (pin "3") (pinfunction "3_3") (pintype "passive"))
      (node (ref "CN2") (pin "4") (pinfunction "4_4") (pintype "passive"))
      (node (ref "P2") (pin "13") (pinfunction "13_13") (pintype "passive"))
      (node (ref "P2") (pin "14") (pinfunction "14_14") (pintype "passive"))
      (node (ref "P2") (pin "15") (pinfunction "15_15") (pintype "passive"))
      (node (ref "R3") (pin "1") (pinfunction "1_1") (pintype "passive"))
      (node (ref "R6") (pin "1") (pinfunction "1_1") (pintype "passive"))
      (node (ref "U3") (pin "44") (pinfunction "44_44") (pintype "passive"))
    )
    (net (code "200") (name "GND_RF3") (class "Default")
      (node (ref "CN1") (pin "5") (pinfunction "5_5") (pintype "passive"))
      (node (ref "CN2") (pin "6") (pinfunction "6_6") (pintype "passive"))
      (node (ref "P3") (pin "13") (pinfunction "13_13") (pintype "passive"))
      (node (ref "P3") (pin "14") (pinfunction "14_14") (pintype "passive"))
      (node (ref "P3") (pin "15") (pinfunction "15_15") (pintype "passive"))
      (node (ref "R7") (pin "1") (pinfunction "1_1") (pintype "passive"))
      (node (ref "R9") (pin "1") (pinfunction "1_1") (pintype "passive"))
      (node (ref "U3") (pin "38") (pinfunction "38_38") (pintype "passive"))
    )
    (net (code "201") (name "GND_RF4") (class "Default")
      (node (ref "CN1") (pin "7") (pinfunction "7_7") (pintype "passive"))
      (node (ref "CN2") (pin "8") (pinfunction "8_8") (pintype "passive"))
      (node (ref "P4") (pin "13") (pinfunction "13_13") (pintype "passive"))
      (node (ref "P4") (pin "14") (pinfunction "14_14") (pintype "passive"))
      (node (ref "P4") (pin "15") (pinfunction "15_15") (pintype "passive"))
      (node (ref "R10") (pin "1") (pinfunction "1_1") (pintype "passive"))
      (node (ref "R13") (pin "1") (pinfunction "1_1") (pintype "passive"))
      (node (ref "U3") (pin "32") (pinfunction "32_32") (pintype "passive"))
    )
    (net (code "202") (name "GND_RF5") (class "Default")
      (node (ref "CN1") (pin "9") (pinfunction "9_9") (pintype "passive"))
      (node (ref "CN2") (pin "10") (pinfunction "10_10") (pintype "passive"))
      (node (ref "P5") (pin "13") (pinfunction "13_13") (pintype "passive"))
      (node (ref "P5") (pin "14") (pinfunction "14_14") (pintype "passive"))
      (node (ref "P5") (pin "15") (pinfunction "15_15") (pintype "passive"))
      (node (ref "R14") (pin "1") (pinfunction "1_1") (pintype "passive"))
      (node (ref "R16") (pin "1") (pinfunction "1_1") (pintype "passive"))
      (node (ref "U3") (pin "24") (pinfunction "24_24") (pintype "passive"))
    )
    (net (code "203") (name "GND_RF6") (class "Default")
      (node (ref "CN1") (pin "11") (pinfunction "11_11") (pintype "passive"))
      (node (ref "CN2") (pin "12") (pinfunction "12_12") (pintype "passive"))
      (node (ref "P6") (pin "13") (pinfunction "13_13") (pintype "passive"))
      (node (ref "P6") (pin "14") (pinfunction "14_14") (pintype "passive"))
      (node (ref "P6") (pin "15") (pinfunction "15_15") (pintype "passive"))
      (node (ref "R17") (pin "1") (pinfunction "1_1") (pintype "passive"))
      (node (ref "R20") (pin "1") (pinfunction "1_1") (pintype "passive"))
      (node (ref "U3") (pin "18") (pinfunction "18_18") (pintype "passive"))
    )
    (net (code "204") (name "GND_RF7") (class "Default")
      (node (ref "CN1") (pin "13") (pinfunction "13_13") (pintype "passive"))
      (node (ref "CN2") (pin "14") (pinfunction "14_14") (pintype "passive"))
      (node (ref "P7") (pin "13") (pinfunction "13_13") (pintype "passive"))
      (node (ref "P7") (pin "14") (pinfunction "14_14") (pintype "passive"))
      (node (ref "P7") (pin "15") (pinfunction "15_15") (pintype "passive"))
      (node (ref "R21") (pin "1") (pinfunction "1_1") (pintype "passive"))
      (node (ref "R23") (pin "1") (pinfunction "1_1") (pintype "passive"))
      (node (ref "U3") (pin "12") (pinfunction "12_12") (pintype "passive"))
    )
    (net (code "205") (name "GND_RF8") (class "Default")
      (node (ref "CN1") (pin "15") (pinfunction "15_15") (pintype "passive"))
      (node (ref "CN2") (pin "16") (pinfunction "16_16") (pintype "passive"))
      (node (ref "P8") (pin "13") (pinfunction "13_13") (pintype "passive"))
      (node (ref "P8") (pin "14") (pinfunction "14_14") (pintype "passive"))
      (node (ref "P8") (pin "15") (pinfunction "15_15") (pintype "passive"))
      (node (ref "R24") (pin "1") (pinfunction "1_1") (pintype "passive"))
      (node (ref "R27") (pin "1") (pinfunction "1_1") (pintype "passive"))
      (node (ref "U3") (pin "6") (pinfunction "6_6") (pintype "passive"))
    )
    (net (code "206") (name "GND_RF9") (class "Default")
      (node (ref "CN1") (pin "17") (pinfunction "17_17") (pintype "passive"))
      (node (ref "CN2") (pin "18") (pinfunction "18_18") (pintype "passive"))
      (node (ref "P9") (pin "13") (pinfunction "13_13") (pintype "passive"))
      (node (ref "P9") (pin "14") (pinfunction "14_14") (pintype "passive"))
      (node (ref "P9") (pin "15") (pinfunction "15_15") (pintype "passive"))
      (node (ref "R28") (pin "1") (pinfunction "1_1") (pintype "passive"))
      (node (ref "R30") (pin "1") (pinfunction "1_1") (pintype "passive"))
      (node (ref "U2") (pin "50") (pinfunction "50_50") (pintype "passive"))
    )
    (net (code "207") (name "GND_RF10") (class "Default")
      (node (ref "CN1") (pin "19") (pinfunction "19_19") (pintype "passive"))
      (node (ref "CN2") (pin "20") (pinfunction "20_20") (pintype "passive"))
      (node (ref "P10") (pin "13") (pinfunction "13_13") (pintype "passive"))
      (node (ref "P10") (pin "14") (pinfunction "14_14") (pintype "passive"))
      (node (ref "P10") (pin "15") (pinfunction "15_15") (pintype "passive"))
      (node (ref "R31") (pin "1") (pinfunction "1_1") (pintype "passive"))
      (node (ref "R34") (pin "1") (pinfunction "1_1") (pintype "passive"))
      (node (ref "U2") (pin "44") (pinfunction "44_44") (pintype "passive"))
    )
    (net (code "208") (name "GND_RF11") (class "Default")
      (node (ref "CN1") (pin "21") (pinfunction "21_21") (pintype "passive"))
      (node (ref "CN2") (pin "22") (pinfunction "22_22") (pintype "passive"))
      (node (ref "P11") (pin "13") (pinfunction "13_13") (pintype "passive"))
      (node (ref "P11") (pin "14") (pinfunction "14_14") (pintype "passive"))
      (node (ref "P11") (pin "15") (pinfunction "15_15") (pintype "passive"))
      (node (ref "R35") (pin "1") (pinfunction "1_1") (pintype "passive"))
      (node (ref "R37") (pin "1") (pinfunction "1_1") (pintype "passive"))
      (node (ref "U2") (pin "38") (pinfunction "38_38") (pintype "passive"))
    )
    (net (code "209") (name "GND_RF12") (class "Default")
      (node (ref "CN1") (pin "23") (pinfunction "23_23") (pintype "passive"))
      (node (ref "CN2") (pin "24") (pinfunction "24_24") (pintype "passive"))
      (node (ref "P12") (pin "13") (pinfunction "13_13") (pintype "passive"))
      (node (ref "P12") (pin "14") (pinfunction "14_14") (pintype "passive"))
      (node (ref "P12") (pin "15") (pinfunction "15_15") (pintype "passive"))
      (node (ref "R38") (pin "1") (pinfunction "1_1") (pintype "passive"))
      (node (ref "R41") (pin "1") (pinfunction "1_1") (pintype "passive"))
      (node (ref "U2") (pin "32") (pinfunction "32_32") (pintype "passive"))
    )
    (net (code "210") (name "GND_RF13") (class "Default")
      (node (ref "CN1") (pin "25") (pinfunction "25_25") (pintype "passive"))
      (node (ref "CN2") (pin "26") (pinfunction "26_26") (pintype "passive"))
      (node (ref "P13") (pin "13") (pinfunction "13_13") (pintype "passive"))
      (node (ref "P13") (pin "14") (pinfunction "14_14") (pintype "passive"))
      (node (ref "P13") (pin "15") (pinfunction "15_15") (pintype "passive"))
      (node (ref "R42") (pin "1") (pinfunction "1_1") (pintype "passive"))
      (node (ref "R44") (pin "1") (pinfunction "1_1") (pintype "passive"))
      (node (ref "U2") (pin "24") (pinfunction "24_24") (pintype "passive"))
    )
    (net (code "211") (name "GND_RF14") (class "Default")
      (node (ref "CN1") (pin "27") (pinfunction "27_27") (pintype "passive"))
      (node (ref "CN2") (pin "28") (pinfunction "28_28") (pintype "passive"))
      (node (ref "P14") (pin "13") (pinfunction "13_13") (pintype "passive"))
      (node (ref "P14") (pin "14") (pinfunction "14_14") (pintype "passive"))
      (node (ref "P14") (pin "15") (pinfunction "15_15") (pintype "passive"))
      (node (ref "R45") (pin "1") (pinfunction "1_1") (pintype "passive"))
      (node (ref "R48") (pin "1") (pinfunction "1_1") (pintype "passive"))
      (node (ref "U2") (pin "18") (pinfunction "18_18") (pintype "passive"))
    )
    (net (code "212") (name "GND_RF15") (class "Default")
      (node (ref "CN1") (pin "29") (pinfunction "29_29") (pintype "passive"))
      (node (ref "CN2") (pin "30") (pinfunction "30_30") (pintype "passive"))
      (node (ref "P15") (pin "13") (pinfunction "13_13") (pintype "passive"))
      (node (ref "P15") (pin "14") (pinfunction "14_14") (pintype "passive"))
      (node (ref "P15") (pin "15") (pinfunction "15_15") (pintype "passive"))
      (node (ref "R49") (pin "1") (pinfunction "1_1") (pintype "passive"))
      (node (ref "R51") (pin "1") (pinfunction "1_1") (pintype "passive"))
      (node (ref "U2") (pin "12") (pinfunction "12_12") (pintype "passive"))
    )
    (net (code "213") (name "GND_RF16") (class "Default")
      (node (ref "CN1") (pin "31") (pinfunction "31_31") (pintype "passive"))
      (node (ref "CN2") (pin "32") (pinfunction "32_32") (pintype "passive"))
      (node (ref "P16") (pin "13") (pinfunction "13_13") (pintype "passive"))
      (node (ref "P16") (pin "14") (pinfunction "14_14") (pintype "passive"))
      (node (ref "P16") (pin "15") (pinfunction "15_15") (pintype "passive"))
      (node (ref "R52") (pin "1") (pinfunction "1_1") (pintype "passive"))
      (node (ref "R55") (pin "1") (pinfunction "1_1") (pintype "passive"))
      (node (ref "U2") (pin "6") (pinfunction "6_6") (pintype "passive"))
    )
    (net (code "214") (name "GND_RF17") (class "Default")
      (node (ref "CN1") (pin "33") (pinfunction "33_33") (pintype "passive"))
      (node (ref "CN2") (pin "34") (pinfunction "34_34") (pintype "passive"))
      (node (ref "P17") (pin "13") (pinfunction "13_13") (pintype "passive"))
      (node (ref "P17") (pin "14") (pinfunction "14_14") (pintype "passive"))
      (node (ref "P17") (pin "15") (pinfunction "15_15") (pintype "passive"))
      (node (ref "R56") (pin "1") (pinfunction "1_1") (pintype "passive"))
      (node (ref "R58") (pin "1") (pinfunction "1_1") (pintype "passive"))
      (node (ref "U1") (pin "50") (pinfunction "50_50") (pintype "passive"))
    )
    (net (code "215") (name "GND_RF18") (class "Default")
      (node (ref "CN1") (pin "35") (pinfunction "35_35") (pintype "passive"))
      (node (ref "CN2") (pin "36") (pinfunction "36_36") (pintype "passive"))
      (node (ref "P18") (pin "13") (pinfunction "13_13") (pintype "passive"))
      (node (ref "P18") (pin "14") (pinfunction "14_14") (pintype "passive"))
      (node (ref "P18") (pin "15") (pinfunction "15_15") (pintype "passive"))
      (node (ref "R59") (pin "1") (pinfunction "1_1") (pintype "passive"))
      (node (ref "R62") (pin "1") (pinfunction "1_1") (pintype "passive"))
      (node (ref "U1") (pin "44") (pinfunction "44_44") (pintype "passive"))
    )
    (net (code "216") (name "GND_RF19") (class "Default")
      (node (ref "CN1") (pin "37") (pinfunction "37_37") (pintype "passive"))
      (node (ref "CN2") (pin "38") (pinfunction "38_38") (pintype "passive"))
      (node (ref "P19") (pin "13") (pinfunction "13_13") (pintype "passive"))
      (node (ref "P19") (pin "14") (pinfunction "14_14") (pintype "passive"))
      (node (ref "P19") (pin "15") (pinfunction "15_15") (pintype "passive"))
      (node (ref "R63") (pin "1") (pinfunction "1_1") (pintype "passive"))
      (node (ref "R65") (pin "1") (pinfunction "1_1") (pintype "passive"))
      (node (ref "U1") (pin "38") (pinfunction "38_38") (pintype "passive"))
    )
    (net (code "217") (name "GND_RF20") (class "Default")
      (node (ref "CN1") (pin "39") (pinfunction "39_39") (pintype "passive"))
      (node (ref "CN2") (pin "40") (pinfunction "40_40") (pintype "passive"))
      (node (ref "P20") (pin "13") (pinfunction "13_13") (pintype "passive"))
      (node (ref "P20") (pin "14") (pinfunction "14_14") (pintype "passive"))
      (node (ref "P20") (pin "15") (pinfunction "15_15") (pintype "passive"))
      (node (ref "R66") (pin "1") (pinfunction "1_1") (pintype "passive"))
      (node (ref "R69") (pin "1") (pinfunction "1_1") (pintype "passive"))
      (node (ref "U1") (pin "32") (pinfunction "32_32") (pintype "passive"))
    )
    (net (code "218") (name "GND_RF21") (class "Default")
      (node (ref "P21") (pin "13") (pinfunction "13_13") (pintype "passive"))
      (node (ref "P21") (pin "14") (pinfunction "14_14") (pintype "passive"))
      (node (ref "P21") (pin "15") (pinfunction "15_15") (pintype "passive"))
      (node (ref "P25") (pin "9") (pinfunction "9_9") (pintype "passive"))
      (node (ref "P26") (pin "9") (pinfunction "9_9") (pintype "passive"))
      (node (ref "R81") (pin "1") (pinfunction "1_1") (pintype "passive"))
      (node (ref "R83") (pin "1") (pinfunction "1_1") (pintype "passive"))
      (node (ref "U1") (pin "24") (pinfunction "24_24") (pintype "passive"))
    )
    (net (code "219") (name "GND_RF22") (class "Default")
      (node (ref "P22") (pin "13") (pinfunction "13_13") (pintype "passive"))
      (node (ref "P22") (pin "14") (pinfunction "14_14") (pintype "passive"))
      (node (ref "P22") (pin "15") (pinfunction "15_15") (pintype "passive"))
      (node (ref "P25") (pin "10") (pinfunction "10_10") (pintype "passive"))
      (node (ref "P26") (pin "10") (pinfunction "10_10") (pintype "passive"))
      (node (ref "R77") (pin "1") (pinfunction "1_1") (pintype "passive"))
      (node (ref "R80") (pin "1") (pinfunction "1_1") (pintype "passive"))
      (node (ref "U1") (pin "18") (pinfunction "18_18") (pintype "passive"))
    )
    (net (code "220") (name "GND_RF23") (class "Default")
      (node (ref "P23") (pin "13") (pinfunction "13_13") (pintype "passive"))
      (node (ref "P23") (pin "14") (pinfunction "14_14") (pintype "passive"))
      (node (ref "P23") (pin "15") (pinfunction "15_15") (pintype "passive"))
      (node (ref "P25") (pin "11") (pinfunction "11_11") (pintype "passive"))
      (node (ref "P26") (pin "11") (pinfunction "11_11") (pintype "passive"))
      (node (ref "R74") (pin "1") (pinfunction "1_1") (pintype "passive"))
      (node (ref "R76") (pin "1") (pinfunction "1_1") (pintype "passive"))
      (node (ref "U1") (pin "12") (pinfunction "12_12") (pintype "passive"))
    )
    (net (code "221") (name "GND_RF24") (class "Default")
      (node (ref "P24") (pin "13") (pinfunction "13_13") (pintype "passive"))
      (node (ref "P24") (pin "14") (pinfunction "14_14") (pintype "passive"))
      (node (ref "P24") (pin "15") (pinfunction "15_15") (pintype "passive"))
      (node (ref "P25") (pin "12") (pinfunction "12_12") (pintype "passive"))
      (node (ref "P26") (pin "12") (pinfunction "12_12") (pintype "passive"))
      (node (ref "R71") (pin "1") (pinfunction "1_1") (pintype "passive"))
      (node (ref "R73") (pin "1") (pinfunction "1_1") (pintype "passive"))
      (node (ref "U1") (pin "6") (pinfunction "6_6") (pintype "passive"))
    )
    (net (code "222") (name "Net-(CN3-Pad1)") (class "Default")
      (node (ref "CN3") (pin "1") (pinfunction "1_1") (pintype "passive"))
      (node (ref "R1") (pin "2") (pinfunction "2_2") (pintype "passive"))
    )
    (net (code "223") (name "Net-(CN3-Pad3)") (class "Default")
      (node (ref "CN3") (pin "3") (pinfunction "3_3") (pintype "passive"))
      (node (ref "R3") (pin "2") (pinfunction "2_2") (pintype "passive"))
    )
    (net (code "224") (name "Net-(CN3-Pad5)") (class "Default")
      (node (ref "CN3") (pin "5") (pinfunction "5_5") (pintype "passive"))
      (node (ref "R7") (pin "2") (pinfunction "2_2") (pintype "passive"))
    )
    (net (code "225") (name "Net-(CN3-Pad7)") (class "Default")
      (node (ref "CN3") (pin "7") (pinfunction "7_7") (pintype "passive"))
      (node (ref "R10") (pin "2") (pinfunction "2_2") (pintype "passive"))
    )
    (net (code "226") (name "Net-(CN3-Pad9)") (class "Default")
      (node (ref "CN3") (pin "9") (pinfunction "9_9") (pintype "passive"))
      (node (ref "R14") (pin "2") (pinfunction "2_2") (pintype "passive"))
    )
    (net (code "227") (name "Net-(CN3-Pad11)") (class "Default")
      (node (ref "CN3") (pin "11") (pinfunction "11_11") (pintype "passive"))
      (node (ref "R17") (pin "2") (pinfunction "2_2") (pintype "passive"))
    )
    (net (code "228") (name "Net-(CN3-Pad13)") (class "Default")
      (node (ref "CN3") (pin "13") (pinfunction "13_13") (pintype "passive"))
      (node (ref "R21") (pin "2") (pinfunction "2_2") (pintype "passive"))
    )
    (net (code "229") (name "Net-(CN3-Pad15)") (class "Default")
      (node (ref "CN3") (pin "15") (pinfunction "15_15") (pintype "passive"))
      (node (ref "R24") (pin "2") (pinfunction "2_2") (pintype "passive"))
    )
    (net (code "230") (name "Net-(CN3-Pad17)") (class "Default")
      (node (ref "CN3") (pin "17") (pinfunction "17_17") (pintype "passive"))
      (node (ref "R28") (pin "2") (pinfunction "2_2") (pintype "passive"))
    )
    (net (code "231") (name "Net-(CN3-Pad19)") (class "Default")
      (node (ref "CN3") (pin "19") (pinfunction "19_19") (pintype "passive"))
      (node (ref "R31") (pin "2") (pinfunction "2_2") (pintype "passive"))
    )
    (net (code "232") (name "Net-(CN3-Pad21)") (class "Default")
      (node (ref "CN3") (pin "21") (pinfunction "21_21") (pintype "passive"))
      (node (ref "R35") (pin "2") (pinfunction "2_2") (pintype "passive"))
    )
    (net (code "233") (name "Net-(CN3-Pad23)") (class "Default")
      (node (ref "CN3") (pin "23") (pinfunction "23_23") (pintype "passive"))
      (node (ref "R38") (pin "2") (pinfunction "2_2") (pintype "passive"))
    )
    (net (code "234") (name "Net-(CN3-Pad25)") (class "Default")
      (node (ref "CN3") (pin "25") (pinfunction "25_25") (pintype "passive"))
      (node (ref "R42") (pin "2") (pinfunction "2_2") (pintype "passive"))
    )
    (net (code "235") (name "Net-(CN3-Pad27)") (class "Default")
      (node (ref "CN3") (pin "27") (pinfunction "27_27") (pintype "passive"))
      (node (ref "R45") (pin "2") (pinfunction "2_2") (pintype "passive"))
    )
    (net (code "236") (name "Net-(CN3-Pad29)") (class "Default")
      (node (ref "CN3") (pin "29") (pinfunction "29_29") (pintype "passive"))
      (node (ref "R49") (pin "2") (pinfunction "2_2") (pintype "passive"))
    )
    (net (code "237") (name "Net-(CN3-Pad31)") (class "Default")
      (node (ref "CN3") (pin "31") (pinfunction "31_31") (pintype "passive"))
      (node (ref "R52") (pin "2") (pinfunction "2_2") (pintype "passive"))
    )
    (net (code "238") (name "Net-(CN3-Pad33)") (class "Default")
      (node (ref "CN3") (pin "33") (pinfunction "33_33") (pintype "passive"))
      (node (ref "R56") (pin "2") (pinfunction "2_2") (pintype "passive"))
    )
    (net (code "239") (name "Net-(CN3-Pad35)") (class "Default")
      (node (ref "CN3") (pin "35") (pinfunction "35_35") (pintype "passive"))
      (node (ref "R59") (pin "2") (pinfunction "2_2") (pintype "passive"))
    )
    (net (code "240") (name "Net-(CN3-Pad37)") (class "Default")
      (node (ref "CN3") (pin "37") (pinfunction "37_37") (pintype "passive"))
      (node (ref "R63") (pin "2") (pinfunction "2_2") (pintype "passive"))
    )
    (net (code "241") (name "Net-(CN3-Pad39)") (class "Default")
      (node (ref "CN3") (pin "39") (pinfunction "39_39") (pintype "passive"))
      (node (ref "R66") (pin "2") (pinfunction "2_2") (pintype "passive"))
    )
    (net (code "242") (name "Net-(CN4-Pad1)") (class "Default")
      (node (ref "CN4") (pin "1") (pinfunction "1_1") (pintype "passive"))
      (node (ref "R2") (pin "2") (pinfunction "2_2") (pintype "passive"))
    )
    (net (code "243") (name "Net-(CN4-Pad3)") (class "Default")
      (node (ref "CN4") (pin "3") (pinfunction "3_3") (pintype "passive"))
      (node (ref "R6") (pin "2") (pinfunction "2_2") (pintype "passive"))
    )
    (net (code "244") (name "Net-(CN4-Pad5)") (class "Default")
      (node (ref "CN4") (pin "5") (pinfunction "5_5") (pintype "passive"))
      (node (ref "R9") (pin "2") (pinfunction "2_2") (pintype "passive"))
    )
    (net (code "245") (name "Net-(CN4-Pad7)") (class "Default")
      (node (ref "CN4") (pin "7") (pinfunction "7_7") (pintype "passive"))
      (node (ref "R13") (pin "2") (pinfunction "2_2") (pintype "passive"))
    )
    (net (code "246") (name "Net-(CN4-Pad9)") (class "Default")
      (node (ref "CN4") (pin "9") (pinfunction "9_9") (pintype "passive"))
      (node (ref "R16") (pin "2") (pinfunction "2_2") (pintype "passive"))
    )
    (net (code "247") (name "Net-(CN4-Pad11)") (class "Default")
      (node (ref "CN4") (pin "11") (pinfunction "11_11") (pintype "passive"))
      (node (ref "R20") (pin "2") (pinfunction "2_2") (pintype "passive"))
    )
    (net (code "248") (name "Net-(CN4-Pad13)") (class "Default")
      (node (ref "CN4") (pin "13") (pinfunction "13_13") (pintype "passive"))
      (node (ref "R23") (pin "2") (pinfunction "2_2") (pintype "passive"))
    )
    (net (code "249") (name "Net-(CN4-Pad15)") (class "Default")
      (node (ref "CN4") (pin "15") (pinfunction "15_15") (pintype "passive"))
      (node (ref "R27") (pin "2") (pinfunction "2_2") (pintype "passive"))
    )
    (net (code "250") (name "Net-(CN4-Pad17)") (class "Default")
      (node (ref "CN4") (pin "17") (pinfunction "17_17") (pintype "passive"))
      (node (ref "R30") (pin "2") (pinfunction "2_2") (pintype "passive"))
    )
    (net (code "251") (name "Net-(CN4-Pad19)") (class "Default")
      (node (ref "CN4") (pin "19") (pinfunction "19_19") (pintype "passive"))
      (node (ref "R34") (pin "2") (pinfunction "2_2") (pintype "passive"))
    )
    (net (code "252") (name "Net-(CN4-Pad21)") (class "Default")
      (node (ref "CN4") (pin "21") (pinfunction "21_21") (pintype "passive"))
      (node (ref "R37") (pin "2") (pinfunction "2_2") (pintype "passive"))
    )
    (net (code "253") (name "Net-(CN4-Pad23)") (class "Default")
      (node (ref "CN4") (pin "23") (pinfunction "23_23") (pintype "passive"))
      (node (ref "R41") (pin "2") (pinfunction "2_2") (pintype "passive"))
    )
    (net (code "254") (name "Net-(CN4-Pad25)") (class "Default")
      (node (ref "CN4") (pin "25") (pinfunction "25_25") (pintype "passive"))
      (node (ref "R44") (pin "2") (pinfunction "2_2") (pintype "passive"))
    )
    (net (code "255") (name "Net-(CN4-Pad27)") (class "Default")
      (node (ref "CN4") (pin "27") (pinfunction "27_27") (pintype "passive"))
      (node (ref "R48") (pin "2") (pinfunction "2_2") (pintype "passive"))
    )
    (net (code "256") (name "Net-(CN4-Pad29)") (class "Default")
      (node (ref "CN4") (pin "29") (pinfunction "29_29") (pintype "passive"))
      (node (ref "R51") (pin "2") (pinfunction "2_2") (pintype "passive"))
    )
    (net (code "257") (name "Net-(CN4-Pad31)") (class "Default")
      (node (ref "CN4") (pin "31") (pinfunction "31_31") (pintype "passive"))
      (node (ref "R55") (pin "2") (pinfunction "2_2") (pintype "passive"))
    )
    (net (code "258") (name "Net-(CN4-Pad33)") (class "Default")
      (node (ref "CN4") (pin "33") (pinfunction "33_33") (pintype "passive"))
      (node (ref "R58") (pin "2") (pinfunction "2_2") (pintype "passive"))
    )
    (net (code "259") (name "Net-(CN4-Pad35)") (class "Default")
      (node (ref "CN4") (pin "35") (pinfunction "35_35") (pintype "passive"))
      (node (ref "R62") (pin "2") (pinfunction "2_2") (pintype "passive"))
    )
    (net (code "260") (name "Net-(CN4-Pad37)") (class "Default")
      (node (ref "CN4") (pin "37") (pinfunction "37_37") (pintype "passive"))
      (node (ref "R65") (pin "2") (pinfunction "2_2") (pintype "passive"))
    )
    (net (code "261") (name "Net-(CN4-Pad39)") (class "Default")
      (node (ref "CN4") (pin "39") (pinfunction "39_39") (pintype "passive"))
      (node (ref "R69") (pin "2") (pinfunction "2_2") (pintype "passive"))
    )
    (net (code "262") (name "Net-(P27-Pad9)") (class "Default")
      (node (ref "P27") (pin "9") (pinfunction "9_9") (pintype "passive"))
      (node (ref "R81") (pin "2") (pinfunction "2_2") (pintype "passive"))
    )
    (net (code "263") (name "Net-(P27-Pad10)") (class "Default")
      (node (ref "P27") (pin "10") (pinfunction "10_10") (pintype "passive"))
      (node (ref "R77") (pin "2") (pinfunction "2_2") (pintype "passive"))
    )
    (net (code "264") (name "Net-(P27-Pad11)") (class "Default")
      (node (ref "P27") (pin "11") (pinfunction "11_11") (pintype "passive"))
      (node (ref "R74") (pin "2") (pinfunction "2_2") (pintype "passive"))
    )
    (net (code "265") (name "Net-(P27-Pad12)") (class "Default")
      (node (ref "P27") (pin "12") (pinfunction "12_12") (pintype "passive"))
      (node (ref "R71") (pin "2") (pinfunction "2_2") (pintype "passive"))
    )
    (net (code "266") (name "Net-(P29-Pad9)") (class "Default")
      (node (ref "P29") (pin "9") (pinfunction "9_9") (pintype "passive"))
      (node (ref "R83") (pin "2") (pinfunction "2_2") (pintype "passive"))
    )
    (net (code "267") (name "Net-(P29-Pad10)") (class "Default")
      (node (ref "P29") (pin "10") (pinfunction "10_10") (pintype "passive"))
      (node (ref "R80") (pin "2") (pinfunction "2_2") (pintype "passive"))
    )
    (net (code "268") (name "Net-(P29-Pad11)") (class "Default")
      (node (ref "P29") (pin "11") (pinfunction "11_11") (pintype "passive"))
      (node (ref "R76") (pin "2") (pinfunction "2_2") (pintype "passive"))
    )
    (net (code "269") (name "Net-(P29-Pad12)") (class "Default")
      (node (ref "P29") (pin "12") (pinfunction "12_12") (pintype "passive"))
      (node (ref "R73") (pin "2") (pinfunction "2_2") (pintype "passive"))
    )
    (net (code "270") (name "unconnected-(P1-Pad3)") (class "Default")
      (node (ref "P1") (pin "3") (pinfunction "3_3") (pintype "passive"))
    )
    (net (code "271") (name "unconnected-(P1-Pad4)") (class "Default")
      (node (ref "P1") (pin "4") (pinfunction "4_4") (pintype "passive"))
    )
    (net (code "272") (name "unconnected-(P1-Pad7)") (class "Default")
      (node (ref "P1") (pin "7") (pinfunction "7_7") (pintype "passive"))
    )
    (net (code "273") (name "unconnected-(P1-Pad8)") (class "Default")
      (node (ref "P1") (pin "8") (pinfunction "8_8") (pintype "passive"))
    )
    (net (code "274") (name "unconnected-(P1-Pad11)") (class "Default")
      (node (ref "P1") (pin "11") (pinfunction "11_11") (pintype "passive"))
    )
    (net (code "275") (name "unconnected-(P1-Pad12)") (class "Default")
      (node (ref "P1") (pin "12") (pinfunction "12_12") (pintype "passive"))
    )
    (net (code "276") (name "unconnected-(P1-Pad16)") (class "Default")
      (node (ref "P1") (pin "16") (pinfunction "16_16") (pintype "passive"))
    )
    (net (code "277") (name "unconnected-(P2-Pad3)") (class "Default")
      (node (ref "P2") (pin "3") (pinfunction "3_3") (pintype "passive"))
    )
    (net (code "278") (name "unconnected-(P2-Pad4)") (class "Default")
      (node (ref "P2") (pin "4") (pinfunction "4_4") (pintype "passive"))
    )
    (net (code "279") (name "unconnected-(P2-Pad7)") (class "Default")
      (node (ref "P2") (pin "7") (pinfunction "7_7") (pintype "passive"))
    )
    (net (code "280") (name "unconnected-(P2-Pad8)") (class "Default")
      (node (ref "P2") (pin "8") (pinfunction "8_8") (pintype "passive"))
    )
    (net (code "281") (name "unconnected-(P2-Pad11)") (class "Default")
      (node (ref "P2") (pin "11") (pinfunction "11_11") (pintype "passive"))
    )
    (net (code "282") (name "unconnected-(P2-Pad12)") (class "Default")
      (node (ref "P2") (pin "12") (pinfunction "12_12") (pintype "passive"))
    )
    (net (code "283") (name "unconnected-(P2-Pad16)") (class "Default")
      (node (ref "P2") (pin "16") (pinfunction "16_16") (pintype "passive"))
    )
    (net (code "284") (name "unconnected-(P3-Pad3)") (class "Default")
      (node (ref "P3") (pin "3") (pinfunction "3_3") (pintype "passive"))
    )
    (net (code "285") (name "unconnected-(P3-Pad4)") (class "Default")
      (node (ref "P3") (pin "4") (pinfunction "4_4") (pintype "passive"))
    )
    (net (code "286") (name "unconnected-(P3-Pad7)") (class "Default")
      (node (ref "P3") (pin "7") (pinfunction "7_7") (pintype "passive"))
    )
    (net (code "287") (name "unconnected-(P3-Pad8)") (class "Default")
      (node (ref "P3") (pin "8") (pinfunction "8_8") (pintype "passive"))
    )
    (net (code "288") (name "unconnected-(P3-Pad11)") (class "Default")
      (node (ref "P3") (pin "11") (pinfunction "11_11") (pintype "passive"))
    )
    (net (code "289") (name "unconnected-(P3-Pad12)") (class "Default")
      (node (ref "P3") (pin "12") (pinfunction "12_12") (pintype "passive"))
    )
    (net (code "290") (name "unconnected-(P3-Pad16)") (class "Default")
      (node (ref "P3") (pin "16") (pinfunction "16_16") (pintype "passive"))
    )
    (net (code "291") (name "unconnected-(P4-Pad3)") (class "Default")
      (node (ref "P4") (pin "3") (pinfunction "3_3") (pintype "passive"))
    )
    (net (code "292") (name "unconnected-(P4-Pad4)") (class "Default")
      (node (ref "P4") (pin "4") (pinfunction "4_4") (pintype "passive"))
    )
    (net (code "293") (name "unconnected-(P4-Pad7)") (class "Default")
      (node (ref "P4") (pin "7") (pinfunction "7_7") (pintype "passive"))
    )
    (net (code "294") (name "unconnected-(P4-Pad8)") (class "Default")
      (node (ref "P4") (pin "8") (pinfunction "8_8") (pintype "passive"))
    )
    (net (code "295") (name "unconnected-(P4-Pad11)") (class "Default")
      (node (ref "P4") (pin "11") (pinfunction "11_11") (pintype "passive"))
    )
    (net (code "296") (name "unconnected-(P4-Pad12)") (class "Default")
      (node (ref "P4") (pin "12") (pinfunction "12_12") (pintype "passive"))
    )
    (net (code "297") (name "unconnected-(P4-Pad16)") (class "Default")
      (node (ref "P4") (pin "16") (pinfunction "16_16") (pintype "passive"))
    )
    (net (code "298") (name "unconnected-(P5-Pad3)") (class "Default")
      (node (ref "P5") (pin "3") (pinfunction "3_3") (pintype "passive"))
    )
    (net (code "299") (name "unconnected-(P5-Pad4)") (class "Default")
      (node (ref "P5") (pin "4") (pinfunction "4_4") (pintype "passive"))
    )
    (net (code "300") (name "unconnected-(P5-Pad7)") (class "Default")
      (node (ref "P5") (pin "7") (pinfunction "7_7") (pintype "passive"))
    )
    (net (code "301") (name "unconnected-(P5-Pad8)") (class "Default")
      (node (ref "P5") (pin "8") (pinfunction "8_8") (pintype "passive"))
    )
    (net (code "302") (name "unconnected-(P5-Pad11)") (class "Default")
      (node (ref "P5") (pin "11") (pinfunction "11_11") (pintype "passive"))
    )
    (net (code "303") (name "unconnected-(P5-Pad12)") (class "Default")
      (node (ref "P5") (pin "12") (pinfunction "12_12") (pintype "passive"))
    )
    (net (code "304") (name "unconnected-(P5-Pad16)") (class "Default")
      (node (ref "P5") (pin "16") (pinfunction "16_16") (pintype "passive"))
    )
    (net (code "305") (name "unconnected-(P6-Pad3)") (class "Default")
      (node (ref "P6") (pin "3") (pinfunction "3_3") (pintype "passive"))
    )
    (net (code "306") (name "unconnected-(P6-Pad4)") (class "Default")
      (node (ref "P6") (pin "4") (pinfunction "4_4") (pintype "passive"))
    )
    (net (code "307") (name "unconnected-(P6-Pad7)") (class "Default")
      (node (ref "P6") (pin "7") (pinfunction "7_7") (pintype "passive"))
    )
    (net (code "308") (name "unconnected-(P6-Pad8)") (class "Default")
      (node (ref "P6") (pin "8") (pinfunction "8_8") (pintype "passive"))
    )
    (net (code "309") (name "unconnected-(P6-Pad11)") (class "Default")
      (node (ref "P6") (pin "11") (pinfunction "11_11") (pintype "passive"))
    )
    (net (code "310") (name "unconnected-(P6-Pad12)") (class "Default")
      (node (ref "P6") (pin "12") (pinfunction "12_12") (pintype "passive"))
    )
    (net (code "311") (name "unconnected-(P6-Pad16)") (class "Default")
      (node (ref "P6") (pin "16") (pinfunction "16_16") (pintype "passive"))
    )
    (net (code "312") (name "unconnected-(P7-Pad3)") (class "Default")
      (node (ref "P7") (pin "3") (pinfunction "3_3") (pintype "passive"))
    )
    (net (code "313") (name "unconnected-(P7-Pad4)") (class "Default")
      (node (ref "P7") (pin "4") (pinfunction "4_4") (pintype "passive"))
    )
    (net (code "314") (name "unconnected-(P7-Pad7)") (class "Default")
      (node (ref "P7") (pin "7") (pinfunction "7_7") (pintype "passive"))
    )
    (net (code "315") (name "unconnected-(P7-Pad8)") (class "Default")
      (node (ref "P7") (pin "8") (pinfunction "8_8") (pintype "passive"))
    )
    (net (code "316") (name "unconnected-(P7-Pad11)") (class "Default")
      (node (ref "P7") (pin "11") (pinfunction "11_11") (pintype "passive"))
    )
    (net (code "317") (name "unconnected-(P7-Pad12)") (class "Default")
      (node (ref "P7") (pin "12") (pinfunction "12_12") (pintype "passive"))
    )
    (net (code "318") (name "unconnected-(P7-Pad16)") (class "Default")
      (node (ref "P7") (pin "16") (pinfunction "16_16") (pintype "passive"))
    )
    (net (code "319") (name "unconnected-(P8-Pad3)") (class "Default")
      (node (ref "P8") (pin "3") (pinfunction "3_3") (pintype "passive"))
    )
    (net (code "320") (name "unconnected-(P8-Pad4)") (class "Default")
      (node (ref "P8") (pin "4") (pinfunction "4_4") (pintype "passive"))
    )
    (net (code "321") (name "unconnected-(P8-Pad7)") (class "Default")
      (node (ref "P8") (pin "7") (pinfunction "7_7") (pintype "passive"))
    )
    (net (code "322") (name "unconnected-(P8-Pad8)") (class "Default")
      (node (ref "P8") (pin "8") (pinfunction "8_8") (pintype "passive"))
    )
    (net (code "323") (name "unconnected-(P8-Pad11)") (class "Default")
      (node (ref "P8") (pin "11") (pinfunction "11_11") (pintype "passive"))
    )
    (net (code "324") (name "unconnected-(P8-Pad12)") (class "Default")
      (node (ref "P8") (pin "12") (pinfunction "12_12") (pintype "passive"))
    )
    (net (code "325") (name "unconnected-(P8-Pad16)") (class "Default")
      (node (ref "P8") (pin "16") (pinfunction "16_16") (pintype "passive"))
    )
    (net (code "326") (name "unconnected-(P9-Pad3)") (class "Default")
      (node (ref "P9") (pin "3") (pinfunction "3_3") (pintype "passive"))
    )
    (net (code "327") (name "unconnected-(P9-Pad4)") (class "Default")
      (node (ref "P9") (pin "4") (pinfunction "4_4") (pintype "passive"))
    )
    (net (code "328") (name "unconnected-(P9-Pad7)") (class "Default")
      (node (ref "P9") (pin "7") (pinfunction "7_7") (pintype "passive"))
    )
    (net (code "329") (name "unconnected-(P9-Pad8)") (class "Default")
      (node (ref "P9") (pin "8") (pinfunction "8_8") (pintype "passive"))
    )
    (net (code "330") (name "unconnected-(P9-Pad11)") (class "Default")
      (node (ref "P9") (pin "11") (pinfunction "11_11") (pintype "passive"))
    )
    (net (code "331") (name "unconnected-(P9-Pad12)") (class "Default")
      (node (ref "P9") (pin "12") (pinfunction "12_12") (pintype "passive"))
    )
    (net (code "332") (name "unconnected-(P9-Pad16)") (class "Default")
      (node (ref "P9") (pin "16") (pinfunction "16_16") (pintype "passive"))
    )
    (net (code "333") (name "unconnected-(P10-Pad3)") (class "Default")
      (node (ref "P10") (pin "3") (pinfunction "3_3") (pintype "passive"))
    )
    (net (code "334") (name "unconnected-(P10-Pad4)") (class "Default")
      (node (ref "P10") (pin "4") (pinfunction "4_4") (pintype "passive"))
    )
    (net (code "335") (name "unconnected-(P10-Pad7)") (class "Default")
      (node (ref "P10") (pin "7") (pinfunction "7_7") (pintype "passive"))
    )
    (net (code "336") (name "unconnected-(P10-Pad8)") (class "Default")
      (node (ref "P10") (pin "8") (pinfunction "8_8") (pintype "passive"))
    )
    (net (code "337") (name "unconnected-(P10-Pad11)") (class "Default")
      (node (ref "P10") (pin "11") (pinfunction "11_11") (pintype "passive"))
    )
    (net (code "338") (name "unconnected-(P10-Pad12)") (class "Default")
      (node (ref "P10") (pin "12") (pinfunction "12_12") (pintype "passive"))
    )
    (net (code "339") (name "unconnected-(P10-Pad16)") (class "Default")
      (node (ref "P10") (pin "16") (pinfunction "16_16") (pintype "passive"))
    )
    (net (code "340") (name "unconnected-(P11-Pad3)") (class "Default")
      (node (ref "P11") (pin "3") (pinfunction "3_3") (pintype "passive"))
    )
    (net (code "341") (name "unconnected-(P11-Pad4)") (class "Default")
      (node (ref "P11") (pin "4") (pinfunction "4_4") (pintype "passive"))
    )
    (net (code "342") (name "unconnected-(P11-Pad7)") (class "Default")
      (node (ref "P11") (pin "7") (pinfunction "7_7") (pintype "passive"))
    )
    (net (code "343") (name "unconnected-(P11-Pad8)") (class "Default")
      (node (ref "P11") (pin "8") (pinfunction "8_8") (pintype "passive"))
    )
    (net (code "344") (name "unconnected-(P11-Pad11)") (class "Default")
      (node (ref "P11") (pin "11") (pinfunction "11_11") (pintype "passive"))
    )
    (net (code "345") (name "unconnected-(P11-Pad12)") (class "Default")
      (node (ref "P11") (pin "12") (pinfunction "12_12") (pintype "passive"))
    )
    (net (code "346") (name "unconnected-(P11-Pad16)") (class "Default")
      (node (ref "P11") (pin "16") (pinfunction "16_16") (pintype "passive"))
    )
    (net (code "347") (name "unconnected-(P12-Pad3)") (class "Default")
      (node (ref "P12") (pin "3") (pinfunction "3_3") (pintype "passive"))
    )
    (net (code "348") (name "unconnected-(P12-Pad4)") (class "Default")
      (node (ref "P12") (pin "4") (pinfunction "4_4") (pintype "passive"))
    )
    (net (code "349") (name "unconnected-(P12-Pad7)") (class "Default")
      (node (ref "P12") (pin "7") (pinfunction "7_7") (pintype "passive"))
    )
    (net (code "350") (name "unconnected-(P12-Pad8)") (class "Default")
      (node (ref "P12") (pin "8") (pinfunction "8_8") (pintype "passive"))
    )
    (net (code "351") (name "unconnected-(P12-Pad11)") (class "Default")
      (node (ref "P12") (pin "11") (pinfunction "11_11") (pintype "passive"))
    )
    (net (code "352") (name "unconnected-(P12-Pad12)") (class "Default")
      (node (ref "P12") (pin "12") (pinfunction "12_12") (pintype "passive"))
    )
    (net (code "353") (name "unconnected-(P12-Pad16)") (class "Default")
      (node (ref "P12") (pin "16") (pinfunction "16_16") (pintype "passive"))
    )
    (net (code "354") (name "unconnected-(P13-Pad3)") (class "Default")
      (node (ref "P13") (pin "3") (pinfunction "3_3") (pintype "passive"))
    )
    (net (code "355") (name "unconnected-(P13-Pad4)") (class "Default")
      (node (ref "P13") (pin "4") (pinfunction "4_4") (pintype "passive"))
    )
    (net (code "356") (name "unconnected-(P13-Pad7)") (class "Default")
      (node (ref "P13") (pin "7") (pinfunction "7_7") (pintype "passive"))
    )
    (net (code "357") (name "unconnected-(P13-Pad8)") (class "Default")
      (node (ref "P13") (pin "8") (pinfunction "8_8") (pintype "passive"))
    )
    (net (code "358") (name "unconnected-(P13-Pad11)") (class "Default")
      (node (ref "P13") (pin "11") (pinfunction "11_11") (pintype "passive"))
    )
    (net (code "359") (name "unconnected-(P13-Pad12)") (class "Default")
      (node (ref "P13") (pin "12") (pinfunction "12_12") (pintype "passive"))
    )
    (net (code "360") (name "unconnected-(P13-Pad16)") (class "Default")
      (node (ref "P13") (pin "16") (pinfunction "16_16") (pintype "passive"))
    )
    (net (code "361") (name "unconnected-(P14-Pad3)") (class "Default")
      (node (ref "P14") (pin "3") (pinfunction "3_3") (pintype "passive"))
    )
    (net (code "362") (name "unconnected-(P14-Pad4)") (class "Default")
      (node (ref "P14") (pin "4") (pinfunction "4_4") (pintype "passive"))
    )
    (net (code "363") (name "unconnected-(P14-Pad7)") (class "Default")
      (node (ref "P14") (pin "7") (pinfunction "7_7") (pintype "passive"))
    )
    (net (code "364") (name "unconnected-(P14-Pad8)") (class "Default")
      (node (ref "P14") (pin "8") (pinfunction "8_8") (pintype "passive"))
    )
    (net (code "365") (name "unconnected-(P14-Pad11)") (class "Default")
      (node (ref "P14") (pin "11") (pinfunction "11_11") (pintype "passive"))
    )
    (net (code "366") (name "unconnected-(P14-Pad12)") (class "Default")
      (node (ref "P14") (pin "12") (pinfunction "12_12") (pintype "passive"))
    )
    (net (code "367") (name "unconnected-(P14-Pad16)") (class "Default")
      (node (ref "P14") (pin "16") (pinfunction "16_16") (pintype "passive"))
    )
    (net (code "368") (name "unconnected-(P15-Pad3)") (class "Default")
      (node (ref "P15") (pin "3") (pinfunction "3_3") (pintype "passive"))
    )
    (net (code "369") (name "unconnected-(P15-Pad4)") (class "Default")
      (node (ref "P15") (pin "4") (pinfunction "4_4") (pintype "passive"))
    )
    (net (code "370") (name "unconnected-(P15-Pad7)") (class "Default")
      (node (ref "P15") (pin "7") (pinfunction "7_7") (pintype "passive"))
    )
    (net (code "371") (name "unconnected-(P15-Pad8)") (class "Default")
      (node (ref "P15") (pin "8") (pinfunction "8_8") (pintype "passive"))
    )
    (net (code "372") (name "unconnected-(P15-Pad11)") (class "Default")
      (node (ref "P15") (pin "11") (pinfunction "11_11") (pintype "passive"))
    )
    (net (code "373") (name "unconnected-(P15-Pad12)") (class "Default")
      (node (ref "P15") (pin "12") (pinfunction "12_12") (pintype "passive"))
    )
    (net (code "374") (name "unconnected-(P15-Pad16)") (class "Default")
      (node (ref "P15") (pin "16") (pinfunction "16_16") (pintype "passive"))
    )
    (net (code "375") (name "unconnected-(P16-Pad3)") (class "Default")
      (node (ref "P16") (pin "3") (pinfunction "3_3") (pintype "passive"))
    )
    (net (code "376") (name "unconnected-(P16-Pad4)") (class "Default")
      (node (ref "P16") (pin "4") (pinfunction "4_4") (pintype "passive"))
    )
    (net (code "377") (name "unconnected-(P16-Pad7)") (class "Default")
      (node (ref "P16") (pin "7") (pinfunction "7_7") (pintype "passive"))
    )
    (net (code "378") (name "unconnected-(P16-Pad8)") (class "Default")
      (node (ref "P16") (pin "8") (pinfunction "8_8") (pintype "passive"))
    )
    (net (code "379") (name "unconnected-(P16-Pad11)") (class "Default")
      (node (ref "P16") (pin "11") (pinfunction "11_11") (pintype "passive"))
    )
    (net (code "380") (name "unconnected-(P16-Pad12)") (class "Default")
      (node (ref "P16") (pin "12") (pinfunction "12_12") (pintype "passive"))
    )
    (net (code "381") (name "unconnected-(P16-Pad16)") (class "Default")
      (node (ref "P16") (pin "16") (pinfunction "16_16") (pintype "passive"))
    )
    (net (code "382") (name "unconnected-(P17-Pad3)") (class "Default")
      (node (ref "P17") (pin "3") (pinfunction "3_3") (pintype "passive"))
    )
    (net (code "383") (name "unconnected-(P17-Pad4)") (class "Default")
      (node (ref "P17") (pin "4") (pinfunction "4_4") (pintype "passive"))
    )
    (net (code "384") (name "unconnected-(P17-Pad7)") (class "Default")
      (node (ref "P17") (pin "7") (pinfunction "7_7") (pintype "passive"))
    )
    (net (code "385") (name "unconnected-(P17-Pad8)") (class "Default")
      (node (ref "P17") (pin "8") (pinfunction "8_8") (pintype "passive"))
    )
    (net (code "386") (name "unconnected-(P17-Pad11)") (class "Default")
      (node (ref "P17") (pin "11") (pinfunction "11_11") (pintype "passive"))
    )
    (net (code "387") (name "unconnected-(P17-Pad12)") (class "Default")
      (node (ref "P17") (pin "12") (pinfunction "12_12") (pintype "passive"))
    )
    (net (code "388") (name "unconnected-(P17-Pad16)") (class "Default")
      (node (ref "P17") (pin "16") (pinfunction "16_16") (pintype "passive"))
    )
    (net (code "389") (name "unconnected-(P18-Pad3)") (class "Default")
      (node (ref "P18") (pin "3") (pinfunction "3_3") (pintype "passive"))
    )
    (net (code "390") (name "unconnected-(P18-Pad4)") (class "Default")
      (node (ref "P18") (pin "4") (pinfunction "4_4") (pintype "passive"))
    )
    (net (code "391") (name "unconnected-(P18-Pad7)") (class "Default")
      (node (ref "P18") (pin "7") (pinfunction "7_7") (pintype "passive"))
    )
    (net (code "392") (name "unconnected-(P18-Pad8)") (class "Default")
      (node (ref "P18") (pin "8") (pinfunction "8_8") (pintype "passive"))
    )
    (net (code "393") (name "unconnected-(P18-Pad11)") (class "Default")
      (node (ref "P18") (pin "11") (pinfunction "11_11") (pintype "passive"))
    )
    (net (code "394") (name "unconnected-(P18-Pad12)") (class "Default")
      (node (ref "P18") (pin "12") (pinfunction "12_12") (pintype "passive"))
    )
    (net (code "395") (name "unconnected-(P18-Pad16)") (class "Default")
      (node (ref "P18") (pin "16") (pinfunction "16_16") (pintype "passive"))
    )
    (net (code "396") (name "unconnected-(P19-Pad3)") (class "Default")
      (node (ref "P19") (pin "3") (pinfunction "3_3") (pintype "passive"))
    )
    (net (code "397") (name "unconnected-(P19-Pad4)") (class "Default")
      (node (ref "P19") (pin "4") (pinfunction "4_4") (pintype "passive"))
    )
    (net (code "398") (name "unconnected-(P19-Pad7)") (class "Default")
      (node (ref "P19") (pin "7") (pinfunction "7_7") (pintype "passive"))
    )
    (net (code "399") (name "unconnected-(P19-Pad8)") (class "Default")
      (node (ref "P19") (pin "8") (pinfunction "8_8") (pintype "passive"))
    )
    (net (code "400") (name "unconnected-(P19-Pad11)") (class "Default")
      (node (ref "P19") (pin "11") (pinfunction "11_11") (pintype "passive"))
    )
    (net (code "401") (name "unconnected-(P19-Pad12)") (class "Default")
      (node (ref "P19") (pin "12") (pinfunction "12_12") (pintype "passive"))
    )
    (net (code "402") (name "unconnected-(P19-Pad16)") (class "Default")
      (node (ref "P19") (pin "16") (pinfunction "16_16") (pintype "passive"))
    )
    (net (code "403") (name "unconnected-(P20-Pad3)") (class "Default")
      (node (ref "P20") (pin "3") (pinfunction "3_3") (pintype "passive"))
    )
    (net (code "404") (name "unconnected-(P20-Pad4)") (class "Default")
      (node (ref "P20") (pin "4") (pinfunction "4_4") (pintype "passive"))
    )
    (net (code "405") (name "unconnected-(P20-Pad7)") (class "Default")
      (node (ref "P20") (pin "7") (pinfunction "7_7") (pintype "passive"))
    )
    (net (code "406") (name "unconnected-(P20-Pad8)") (class "Default")
      (node (ref "P20") (pin "8") (pinfunction "8_8") (pintype "passive"))
    )
    (net (code "407") (name "unconnected-(P20-Pad11)") (class "Default")
      (node (ref "P20") (pin "11") (pinfunction "11_11") (pintype "passive"))
    )
    (net (code "408") (name "unconnected-(P20-Pad12)") (class "Default")
      (node (ref "P20") (pin "12") (pinfunction "12_12") (pintype "passive"))
    )
    (net (code "409") (name "unconnected-(P20-Pad16)") (class "Default")
      (node (ref "P20") (pin "16") (pinfunction "16_16") (pintype "passive"))
    )
    (net (code "410") (name "unconnected-(P21-Pad3)") (class "Default")
      (node (ref "P21") (pin "3") (pinfunction "3_3") (pintype "passive"))
    )
    (net (code "411") (name "unconnected-(P21-Pad4)") (class "Default")
      (node (ref "P21") (pin "4") (pinfunction "4_4") (pintype "passive"))
    )
    (net (code "412") (name "unconnected-(P21-Pad7)") (class "Default")
      (node (ref "P21") (pin "7") (pinfunction "7_7") (pintype "passive"))
    )
    (net (code "413") (name "unconnected-(P21-Pad8)") (class "Default")
      (node (ref "P21") (pin "8") (pinfunction "8_8") (pintype "passive"))
    )
    (net (code "414") (name "unconnected-(P21-Pad11)") (class "Default")
      (node (ref "P21") (pin "11") (pinfunction "11_11") (pintype "passive"))
    )
    (net (code "415") (name "unconnected-(P21-Pad12)") (class "Default")
      (node (ref "P21") (pin "12") (pinfunction "12_12") (pintype "passive"))
    )
    (net (code "416") (name "unconnected-(P21-Pad16)") (class "Default")
      (node (ref "P21") (pin "16") (pinfunction "16_16") (pintype "passive"))
    )
    (net (code "417") (name "unconnected-(P22-Pad3)") (class "Default")
      (node (ref "P22") (pin "3") (pinfunction "3_3") (pintype "passive"))
    )
    (net (code "418") (name "unconnected-(P22-Pad4)") (class "Default")
      (node (ref "P22") (pin "4") (pinfunction "4_4") (pintype "passive"))
    )
    (net (code "419") (name "unconnected-(P22-Pad7)") (class "Default")
      (node (ref "P22") (pin "7") (pinfunction "7_7") (pintype "passive"))
    )
    (net (code "420") (name "unconnected-(P22-Pad8)") (class "Default")
      (node (ref "P22") (pin "8") (pinfunction "8_8") (pintype "passive"))
    )
    (net (code "421") (name "unconnected-(P22-Pad11)") (class "Default")
      (node (ref "P22") (pin "11") (pinfunction "11_11") (pintype "passive"))
    )
    (net (code "422") (name "unconnected-(P22-Pad12)") (class "Default")
      (node (ref "P22") (pin "12") (pinfunction "12_12") (pintype "passive"))
    )
    (net (code "423") (name "unconnected-(P22-Pad16)") (class "Default")
      (node (ref "P22") (pin "16") (pinfunction "16_16") (pintype "passive"))
    )
    (net (code "424") (name "unconnected-(P23-Pad3)") (class "Default")
      (node (ref "P23") (pin "3") (pinfunction "3_3") (pintype "passive"))
    )
    (net (code "425") (name "unconnected-(P23-Pad4)") (class "Default")
      (node (ref "P23") (pin "4") (pinfunction "4_4") (pintype "passive"))
    )
    (net (code "426") (name "unconnected-(P23-Pad7)") (class "Default")
      (node (ref "P23") (pin "7") (pinfunction "7_7") (pintype "passive"))
    )
    (net (code "427") (name "unconnected-(P23-Pad8)") (class "Default")
      (node (ref "P23") (pin "8") (pinfunction "8_8") (pintype "passive"))
    )
    (net (code "428") (name "unconnected-(P23-Pad11)") (class "Default")
      (node (ref "P23") (pin "11") (pinfunction "11_11") (pintype "passive"))
    )
    (net (code "429") (name "unconnected-(P23-Pad12)") (class "Default")
      (node (ref "P23") (pin "12") (pinfunction "12_12") (pintype "passive"))
    )
    (net (code "430") (name "unconnected-(P23-Pad16)") (class "Default")
      (node (ref "P23") (pin "16") (pinfunction "16_16") (pintype "passive"))
    )
    (net (code "431") (name "unconnected-(P24-Pad3)") (class "Default")
      (node (ref "P24") (pin "3") (pinfunction "3_3") (pintype "passive"))
    )
    (net (code "432") (name "unconnected-(P24-Pad4)") (class "Default")
      (node (ref "P24") (pin "4") (pinfunction "4_4") (pintype "passive"))
    )
    (net (code "433") (name "unconnected-(P24-Pad7)") (class "Default")
      (node (ref "P24") (pin "7") (pinfunction "7_7") (pintype "passive"))
    )
    (net (code "434") (name "unconnected-(P24-Pad8)") (class "Default")
      (node (ref "P24") (pin "8") (pinfunction "8_8") (pintype "passive"))
    )
    (net (code "435") (name "unconnected-(P24-Pad11)") (class "Default")
      (node (ref "P24") (pin "11") (pinfunction "11_11") (pintype "passive"))
    )
    (net (code "436") (name "unconnected-(P24-Pad12)") (class "Default")
      (node (ref "P24") (pin "12") (pinfunction "12_12") (pintype "passive"))
    )
    (net (code "437") (name "unconnected-(P24-Pad16)") (class "Default")
      (node (ref "P24") (pin "16") (pinfunction "16_16") (pintype "passive"))
    )
    (net (code "438") (name "unconnected-(P25-Pad5)") (class "Default")
      (node (ref "P25") (pin "5") (pinfunction "5_5") (pintype "passive"))
    )
    (net (code "439") (name "unconnected-(P25-Pad6)") (class "Default")
      (node (ref "P25") (pin "6") (pinfunction "6_6") (pintype "passive"))
    )
    (net (code "440") (name "unconnected-(P25-Pad7)") (class "Default")
      (node (ref "P25") (pin "7") (pinfunction "7_7") (pintype "passive"))
    )
    (net (code "441") (name "unconnected-(P25-Pad8)") (class "Default")
      (node (ref "P25") (pin "8") (pinfunction "8_8") (pintype "passive"))
    )
    (net (code "442") (name "unconnected-(P25-Pad13)") (class "Default")
      (node (ref "P25") (pin "13") (pinfunction "13_13") (pintype "passive"))
    )
    (net (code "443") (name "unconnected-(P25-Pad14)") (class "Default")
      (node (ref "P25") (pin "14") (pinfunction "14_14") (pintype "passive"))
    )
    (net (code "444") (name "unconnected-(P25-Pad15)") (class "Default")
      (node (ref "P25") (pin "15") (pinfunction "15_15") (pintype "passive"))
    )
    (net (code "445") (name "unconnected-(P25-Pad16)") (class "Default")
      (node (ref "P25") (pin "16") (pinfunction "16_16") (pintype "passive"))
    )
    (net (code "446") (name "unconnected-(P26-Pad5)") (class "Default")
      (node (ref "P26") (pin "5") (pinfunction "5_5") (pintype "passive"))
    )
    (net (code "447") (name "unconnected-(P26-Pad6)") (class "Default")
      (node (ref "P26") (pin "6") (pinfunction "6_6") (pintype "passive"))
    )
    (net (code "448") (name "unconnected-(P26-Pad7)") (class "Default")
      (node (ref "P26") (pin "7") (pinfunction "7_7") (pintype "passive"))
    )
    (net (code "449") (name "unconnected-(P26-Pad8)") (class "Default")
      (node (ref "P26") (pin "8") (pinfunction "8_8") (pintype "passive"))
    )
    (net (code "450") (name "unconnected-(P26-Pad13)") (class "Default")
      (node (ref "P26") (pin "13") (pinfunction "13_13") (pintype "passive"))
    )
    (net (code "451") (name "unconnected-(P26-Pad14)") (class "Default")
      (node (ref "P26") (pin "14") (pinfunction "14_14") (pintype "passive"))
    )
    (net (code "452") (name "unconnected-(P26-Pad15)") (class "Default")
      (node (ref "P26") (pin "15") (pinfunction "15_15") (pintype "passive"))
    )
    (net (code "453") (name "unconnected-(P26-Pad16)") (class "Default")
      (node (ref "P26") (pin "16") (pinfunction "16_16") (pintype "passive"))
    )
    (net (code "454") (name "unconnected-(P27-Pad5)") (class "Default")
      (node (ref "P27") (pin "5") (pinfunction "5_5") (pintype "passive"))
    )
    (net (code "455") (name "unconnected-(P27-Pad6)") (class "Default")
      (node (ref "P27") (pin "6") (pinfunction "6_6") (pintype "passive"))
    )
    (net (code "456") (name "unconnected-(P27-Pad7)") (class "Default")
      (node (ref "P27") (pin "7") (pinfunction "7_7") (pintype "passive"))
    )
    (net (code "457") (name "unconnected-(P27-Pad8)") (class "Default")
      (node (ref "P27") (pin "8") (pinfunction "8_8") (pintype "passive"))
    )
    (net (code "458") (name "unconnected-(P27-Pad13)") (class "Default")
      (node (ref "P27") (pin "13") (pinfunction "13_13") (pintype "passive"))
    )
    (net (code "459") (name "unconnected-(P27-Pad14)") (class "Default")
      (node (ref "P27") (pin "14") (pinfunction "14_14") (pintype "passive"))
    )
    (net (code "460") (name "unconnected-(P27-Pad15)") (class "Default")
      (node (ref "P27") (pin "15") (pinfunction "15_15") (pintype "passive"))
    )
    (net (code "461") (name "unconnected-(P27-Pad16)") (class "Default")
      (node (ref "P27") (pin "16") (pinfunction "16_16") (pintype "passive"))
    )
    (net (code "462") (name "unconnected-(P28-Pad5)") (class "Default")
      (node (ref "P28") (pin "5") (pinfunction "5_5") (pintype "passive"))
    )
    (net (code "463") (name "unconnected-(P28-Pad6)") (class "Default")
      (node (ref "P28") (pin "6") (pinfunction "6_6") (pintype "passive"))
    )
    (net (code "464") (name "unconnected-(P28-Pad7)") (class "Default")
      (node (ref "P28") (pin "7") (pinfunction "7_7") (pintype "passive"))
    )
    (net (code "465") (name "unconnected-(P28-Pad8)") (class "Default")
      (node (ref "P28") (pin "8") (pinfunction "8_8") (pintype "passive"))
    )
    (net (code "466") (name "unconnected-(P28-Pad13)") (class "Default")
      (node (ref "P28") (pin "13") (pinfunction "13_13") (pintype "passive"))
    )
    (net (code "467") (name "unconnected-(P28-Pad14)") (class "Default")
      (node (ref "P28") (pin "14") (pinfunction "14_14") (pintype "passive"))
    )
    (net (code "468") (name "unconnected-(P28-Pad15)") (class "Default")
      (node (ref "P28") (pin "15") (pinfunction "15_15") (pintype "passive"))
    )
    (net (code "469") (name "unconnected-(P28-Pad16)") (class "Default")
      (node (ref "P28") (pin "16") (pinfunction "16_16") (pintype "passive"))
    )
    (net (code "470") (name "unconnected-(P29-Pad5)") (class "Default")
      (node (ref "P29") (pin "5") (pinfunction "5_5") (pintype "passive"))
    )
    (net (code "471") (name "unconnected-(P29-Pad6)") (class "Default")
      (node (ref "P29") (pin "6") (pinfunction "6_6") (pintype "passive"))
    )
    (net (code "472") (name "unconnected-(P29-Pad7)") (class "Default")
      (node (ref "P29") (pin "7") (pinfunction "7_7") (pintype "passive"))
    )
    (net (code "473") (name "unconnected-(P29-Pad8)") (class "Default")
      (node (ref "P29") (pin "8") (pinfunction "8_8") (pintype "passive"))
    )
    (net (code "474") (name "unconnected-(P29-Pad13)") (class "Default")
      (node (ref "P29") (pin "13") (pinfunction "13_13") (pintype "passive"))
    )
    (net (code "475") (name "unconnected-(P29-Pad14)") (class "Default")
      (node (ref "P29") (pin "14") (pinfunction "14_14") (pintype "passive"))
    )
    (net (code "476") (name "unconnected-(P29-Pad15)") (class "Default")
      (node (ref "P29") (pin "15") (pinfunction "15_15") (pintype "passive"))
    )
    (net (code "477") (name "unconnected-(P29-Pad16)") (class "Default")
      (node (ref "P29") (pin "16") (pinfunction "16_16") (pintype "passive"))
    )
    (net (code "478") (name "unconnected-(U1-Pad1)") (class "Default")
      (node (ref "U1") (pin "1") (pinfunction "1_1") (pintype "passive"))
    )
    (net (code "479") (name "unconnected-(U1-Pad3)") (class "Default")
      (node (ref "U1") (pin "3") (pinfunction "3_3") (pintype "passive"))
    )
    (net (code "480") (name "unconnected-(U1-Pad7)") (class "Default")
      (node (ref "U1") (pin "7") (pinfunction "7_7") (pintype "passive"))
    )
    (net (code "481") (name "unconnected-(U1-Pad9)") (class "Default")
      (node (ref "U1") (pin "9") (pinfunction "9_9") (pintype "passive"))
    )
    (net (code "482") (name "unconnected-(U1-Pad13)") (class "Default")
      (node (ref "U1") (pin "13") (pinfunction "13_13") (pintype "passive"))
    )
    (net (code "483") (name "unconnected-(U1-Pad15)") (class "Default")
      (node (ref "U1") (pin "15") (pinfunction "15_15") (pintype "passive"))
    )
    (net (code "484") (name "unconnected-(U1-Pad19)") (class "Default")
      (node (ref "U1") (pin "19") (pinfunction "19_19") (pintype "passive"))
    )
    (net (code "485") (name "unconnected-(U1-Pad21)") (class "Default")
      (node (ref "U1") (pin "21") (pinfunction "21_21") (pintype "passive"))
    )
    (net (code "486") (name "unconnected-(U1-Pad25)") (class "Default")
      (node (ref "U1") (pin "25") (pinfunction "25_25") (pintype "passive"))
    )
    (net (code "487") (name "unconnected-(U1-Pad26)") (class "Default")
      (node (ref "U1") (pin "26") (pinfunction "26_26") (pintype "passive"))
    )
    (net (code "488") (name "unconnected-(U1-Pad27)") (class "Default")
      (node (ref "U1") (pin "27") (pinfunction "27_27") (pintype "passive"))
    )
    (net (code "489") (name "unconnected-(U1-Pad29)") (class "Default")
      (node (ref "U1") (pin "29") (pinfunction "29_29") (pintype "passive"))
    )
    (net (code "490") (name "unconnected-(U1-Pad33)") (class "Default")
      (node (ref "U1") (pin "33") (pinfunction "33_33") (pintype "passive"))
    )
    (net (code "491") (name "unconnected-(U1-Pad35)") (class "Default")
      (node (ref "U1") (pin "35") (pinfunction "35_35") (pintype "passive"))
    )
    (net (code "492") (name "unconnected-(U1-Pad39)") (class "Default")
      (node (ref "U1") (pin "39") (pinfunction "39_39") (pintype "passive"))
    )
    (net (code "493") (name "unconnected-(U1-Pad41)") (class "Default")
      (node (ref "U1") (pin "41") (pinfunction "41_41") (pintype "passive"))
    )
    (net (code "494") (name "unconnected-(U1-Pad45)") (class "Default")
      (node (ref "U1") (pin "45") (pinfunction "45_45") (pintype "passive"))
    )
    (net (code "495") (name "unconnected-(U1-Pad47)") (class "Default")
      (node (ref "U1") (pin "47") (pinfunction "47_47") (pintype "passive"))
    )
    (net (code "496") (name "unconnected-(U2-Pad1)") (class "Default")
      (node (ref "U2") (pin "1") (pinfunction "1_1") (pintype "passive"))
    )
    (net (code "497") (name "unconnected-(U2-Pad3)") (class "Default")
      (node (ref "U2") (pin "3") (pinfunction "3_3") (pintype "passive"))
    )
    (net (code "498") (name "unconnected-(U2-Pad7)") (class "Default")
      (node (ref "U2") (pin "7") (pinfunction "7_7") (pintype "passive"))
    )
    (net (code "499") (name "unconnected-(U2-Pad9)") (class "Default")
      (node (ref "U2") (pin "9") (pinfunction "9_9") (pintype "passive"))
    )
    (net (code "500") (name "unconnected-(U2-Pad13)") (class "Default")
      (node (ref "U2") (pin "13") (pinfunction "13_13") (pintype "passive"))
    )
    (net (code "501") (name "unconnected-(U2-Pad15)") (class "Default")
      (node (ref "U2") (pin "15") (pinfunction "15_15") (pintype "passive"))
    )
    (net (code "502") (name "unconnected-(U2-Pad19)") (class "Default")
      (node (ref "U2") (pin "19") (pinfunction "19_19") (pintype "passive"))
    )
    (net (code "503") (name "unconnected-(U2-Pad21)") (class "Default")
      (node (ref "U2") (pin "21") (pinfunction "21_21") (pintype "passive"))
    )
    (net (code "504") (name "unconnected-(U2-Pad25)") (class "Default")
      (node (ref "U2") (pin "25") (pinfunction "25_25") (pintype "passive"))
    )
    (net (code "505") (name "unconnected-(U2-Pad26)") (class "Default")
      (node (ref "U2") (pin "26") (pinfunction "26_26") (pintype "passive"))
    )
    (net (code "506") (name "unconnected-(U2-Pad27)") (class "Default")
      (node (ref "U2") (pin "27") (pinfunction "27_27") (pintype "passive"))
    )
    (net (code "507") (name "unconnected-(U2-Pad29)") (class "Default")
      (node (ref "U2") (pin "29") (pinfunction "29_29") (pintype "passive"))
    )
    (net (code "508") (name "unconnected-(U2-Pad33)") (class "Default")
      (node (ref "U2") (pin "33") (pinfunction "33_33") (pintype "passive"))
    )
    (net (code "509") (name "unconnected-(U2-Pad35)") (class "Default")
      (node (ref "U2") (pin "35") (pinfunction "35_35") (pintype "passive"))
    )
    (net (code "510") (name "unconnected-(U2-Pad39)") (class "Default")
      (node (ref "U2") (pin "39") (pinfunction "39_39") (pintype "passive"))
    )
    (net (code "511") (name "unconnected-(U2-Pad41)") (class "Default")
      (node (ref "U2") (pin "41") (pinfunction "41_41") (pintype "passive"))
    )
    (net (code "512") (name "unconnected-(U2-Pad45)") (class "Default")
      (node (ref "U2") (pin "45") (pinfunction "45_45") (pintype "passive"))
    )
    (net (code "513") (name "unconnected-(U2-Pad47)") (class "Default")
      (node (ref "U2") (pin "47") (pinfunction "47_47") (pintype "passive"))
    )
    (net (code "514") (name "unconnected-(U3-Pad1)") (class "Default")
      (node (ref "U3") (pin "1") (pinfunction "1_1") (pintype "passive"))
    )
    (net (code "515") (name "unconnected-(U3-Pad3)") (class "Default")
      (node (ref "U3") (pin "3") (pinfunction "3_3") (pintype "passive"))
    )
    (net (code "516") (name "unconnected-(U3-Pad7)") (class "Default")
      (node (ref "U3") (pin "7") (pinfunction "7_7") (pintype "passive"))
    )
    (net (code "517") (name "unconnected-(U3-Pad9)") (class "Default")
      (node (ref "U3") (pin "9") (pinfunction "9_9") (pintype "passive"))
    )
    (net (code "518") (name "unconnected-(U3-Pad13)") (class "Default")
      (node (ref "U3") (pin "13") (pinfunction "13_13") (pintype "passive"))
    )
    (net (code "519") (name "unconnected-(U3-Pad15)") (class "Default")
      (node (ref "U3") (pin "15") (pinfunction "15_15") (pintype "passive"))
    )
    (net (code "520") (name "unconnected-(U3-Pad19)") (class "Default")
      (node (ref "U3") (pin "19") (pinfunction "19_19") (pintype "passive"))
    )
    (net (code "521") (name "unconnected-(U3-Pad21)") (class "Default")
      (node (ref "U3") (pin "21") (pinfunction "21_21") (pintype "passive"))
    )
    (net (code "522") (name "unconnected-(U3-Pad25)") (class "Default")
      (node (ref "U3") (pin "25") (pinfunction "25_25") (pintype "passive"))
    )
    (net (code "523") (name "unconnected-(U3-Pad26)") (class "Default")
      (node (ref "U3") (pin "26") (pinfunction "26_26") (pintype "passive"))
    )
    (net (code "524") (name "unconnected-(U3-Pad27)") (class "Default")
      (node (ref "U3") (pin "27") (pinfunction "27_27") (pintype "passive"))
    )
    (net (code "525") (name "unconnected-(U3-Pad29)") (class "Default")
      (node (ref "U3") (pin "29") (pinfunction "29_29") (pintype "passive"))
    )
    (net (code "526") (name "unconnected-(U3-Pad33)") (class "Default")
      (node (ref "U3") (pin "33") (pinfunction "33_33") (pintype "passive"))
    )
    (net (code "527") (name "unconnected-(U3-Pad35)") (class "Default")
      (node (ref "U3") (pin "35") (pinfunction "35_35") (pintype "passive"))
    )
    (net (code "528") (name "unconnected-(U3-Pad39)") (class "Default")
      (node (ref "U3") (pin "39") (pinfunction "39_39") (pintype "passive"))
    )
    (net (code "529") (name "unconnected-(U3-Pad41)") (class "Default")
      (node (ref "U3") (pin "41") (pinfunction "41_41") (pintype "passive"))
    )
    (net (code "530") (name "unconnected-(U3-Pad45)") (class "Default")
      (node (ref "U3") (pin "45") (pinfunction "45_45") (pintype "passive"))
    )
    (net (code "531") (name "unconnected-(U3-Pad47)") (class "Default")
      (node (ref "U3") (pin "47") (pinfunction "47_47") (pintype "passive"))
    )
  )
)
